# GMSL_DESERIALIZER.net
KiCad netlist of a schematic drawn in Altium Designer
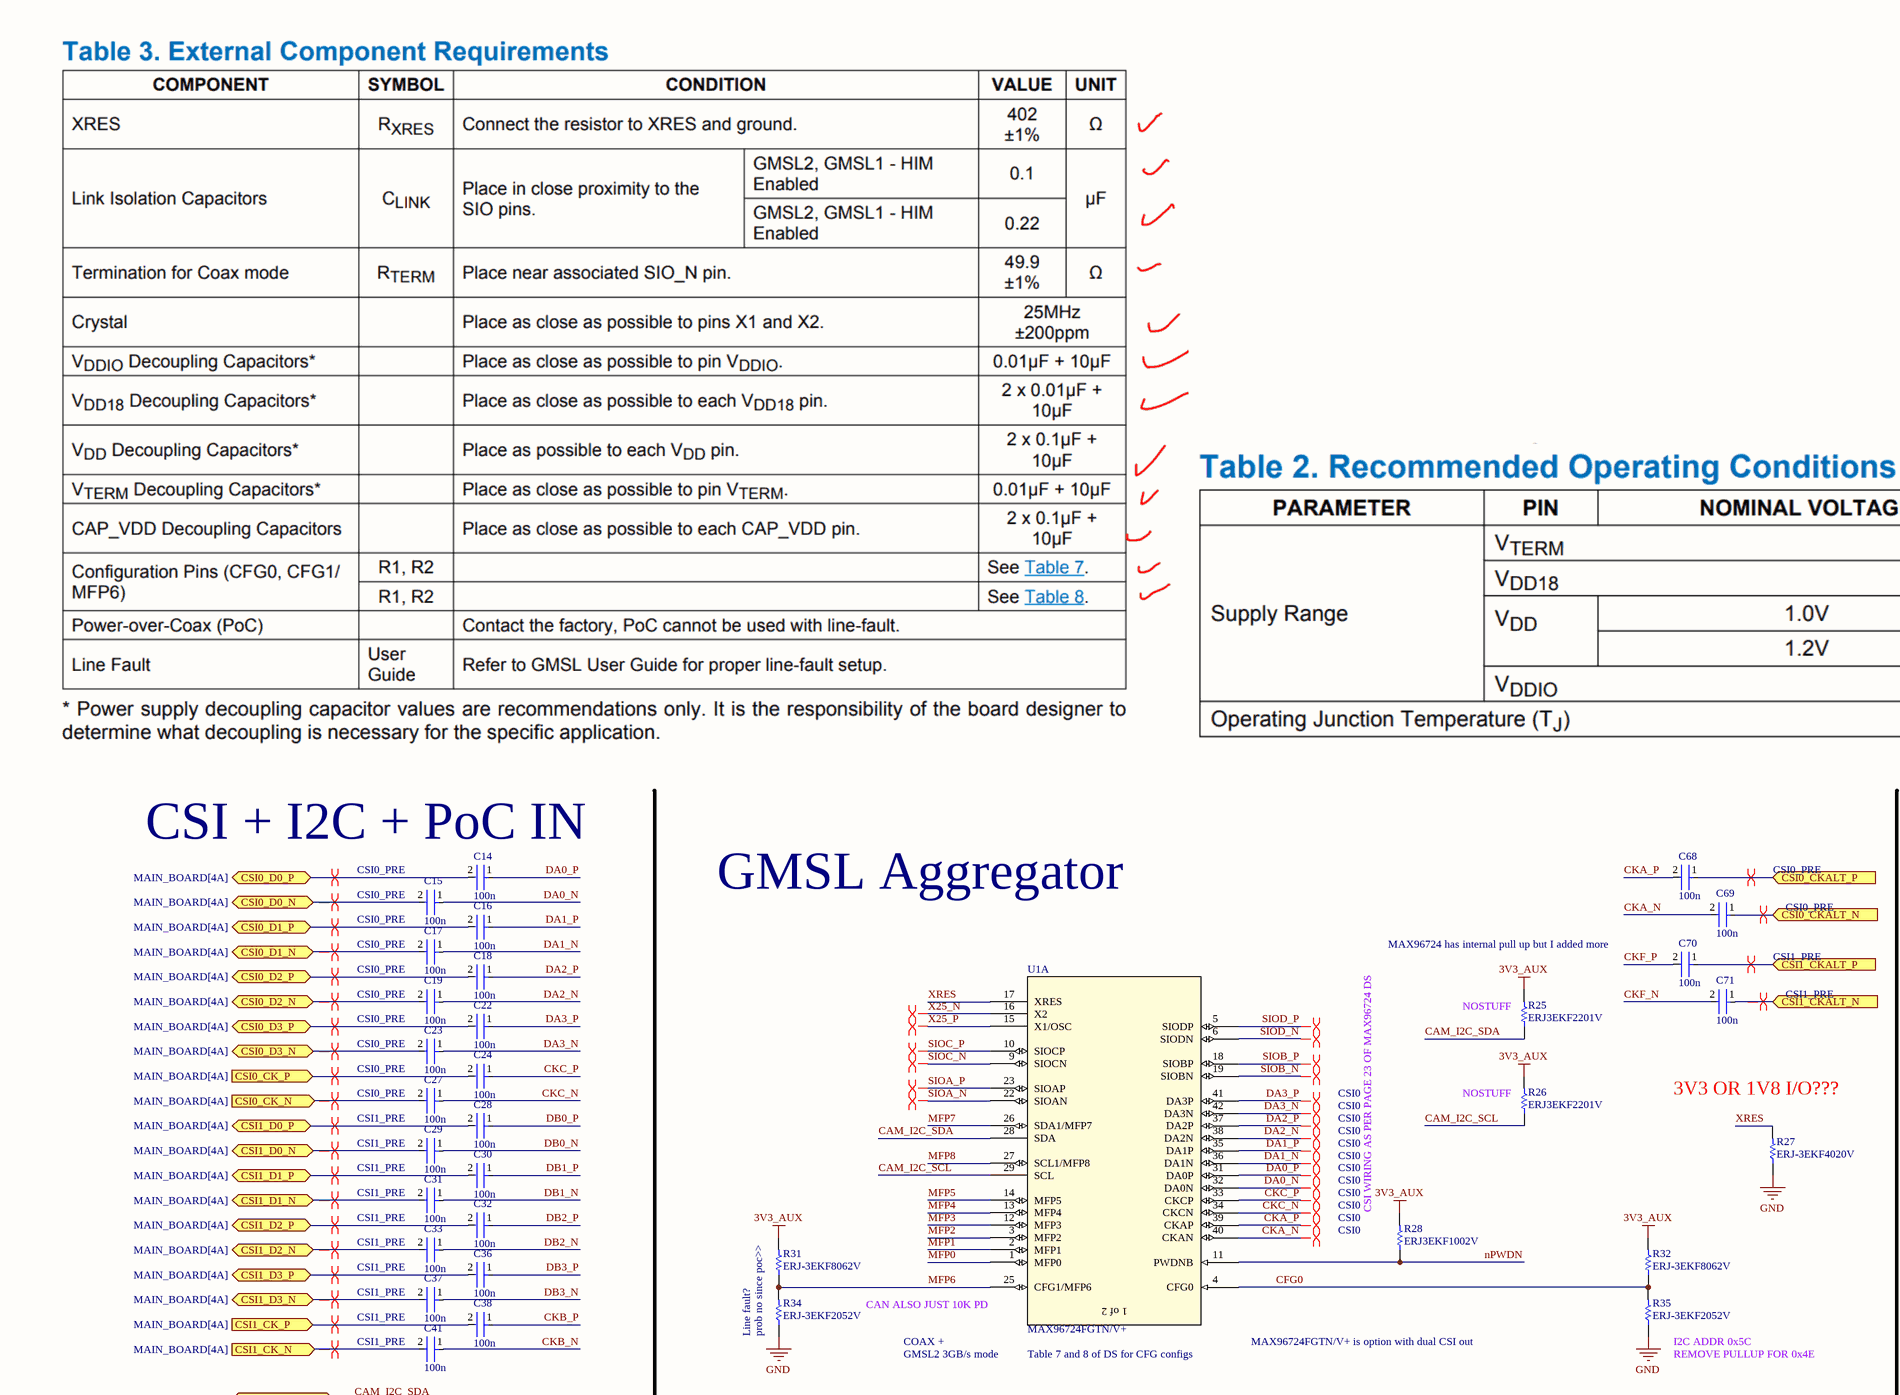
[diagram p0: GMSL_DESERIALIZER.SchDoc, top left]
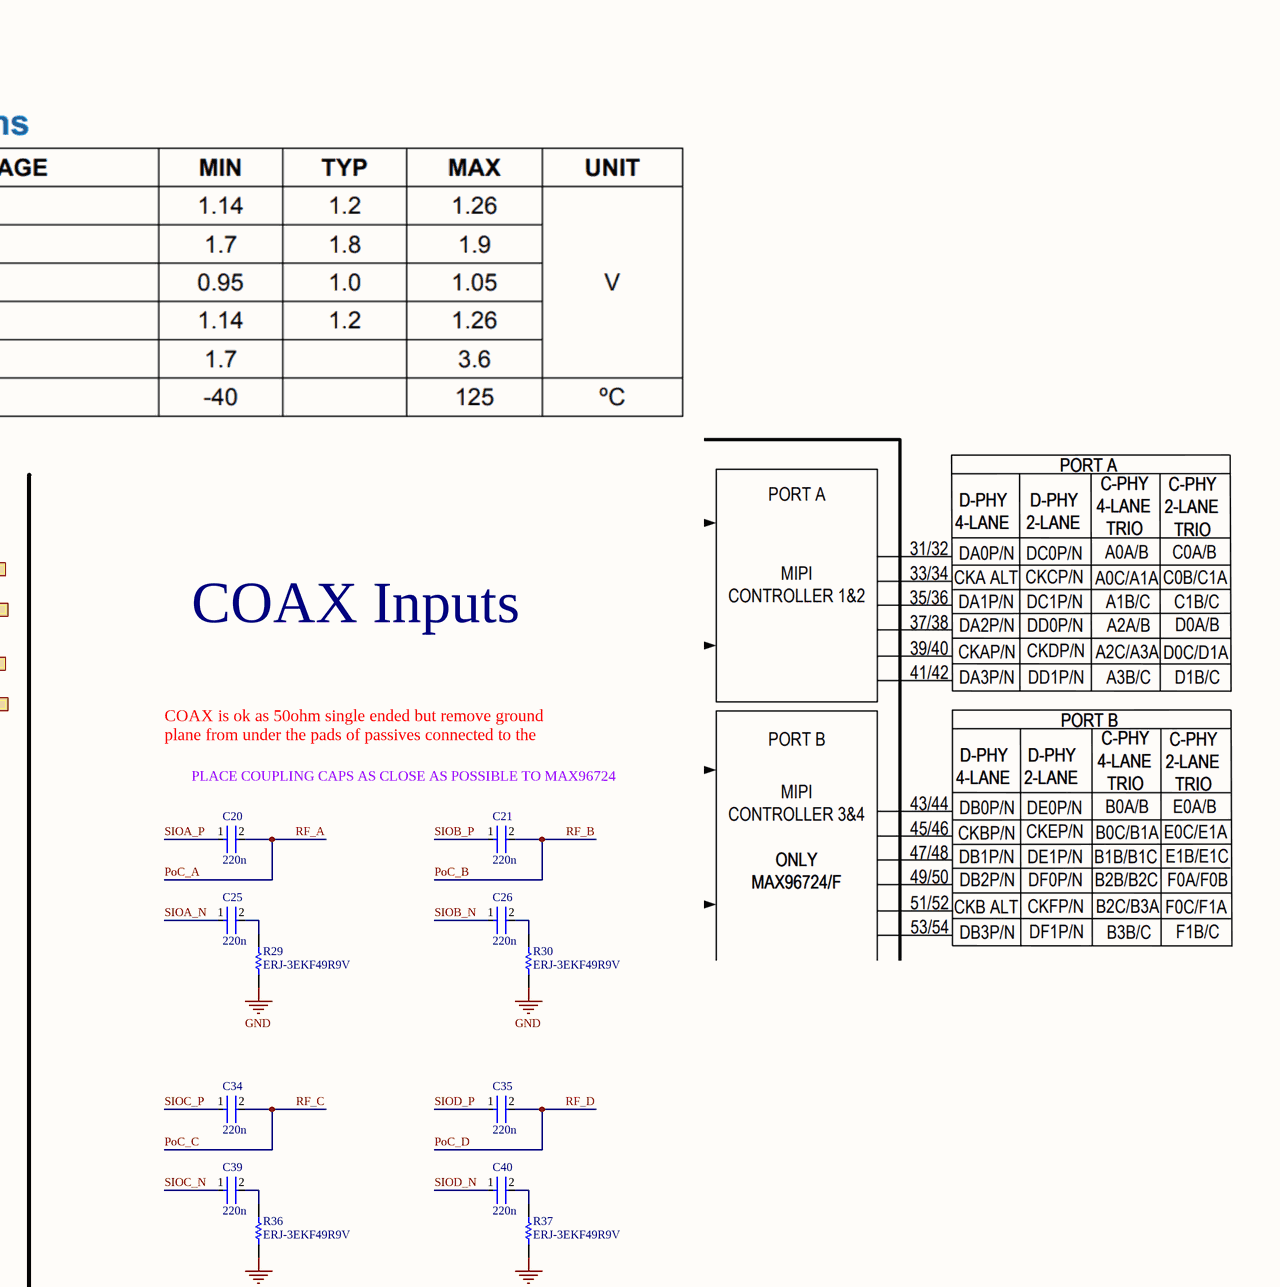
[diagram p1: GMSL_DESERIALIZER.SchDoc, top right]
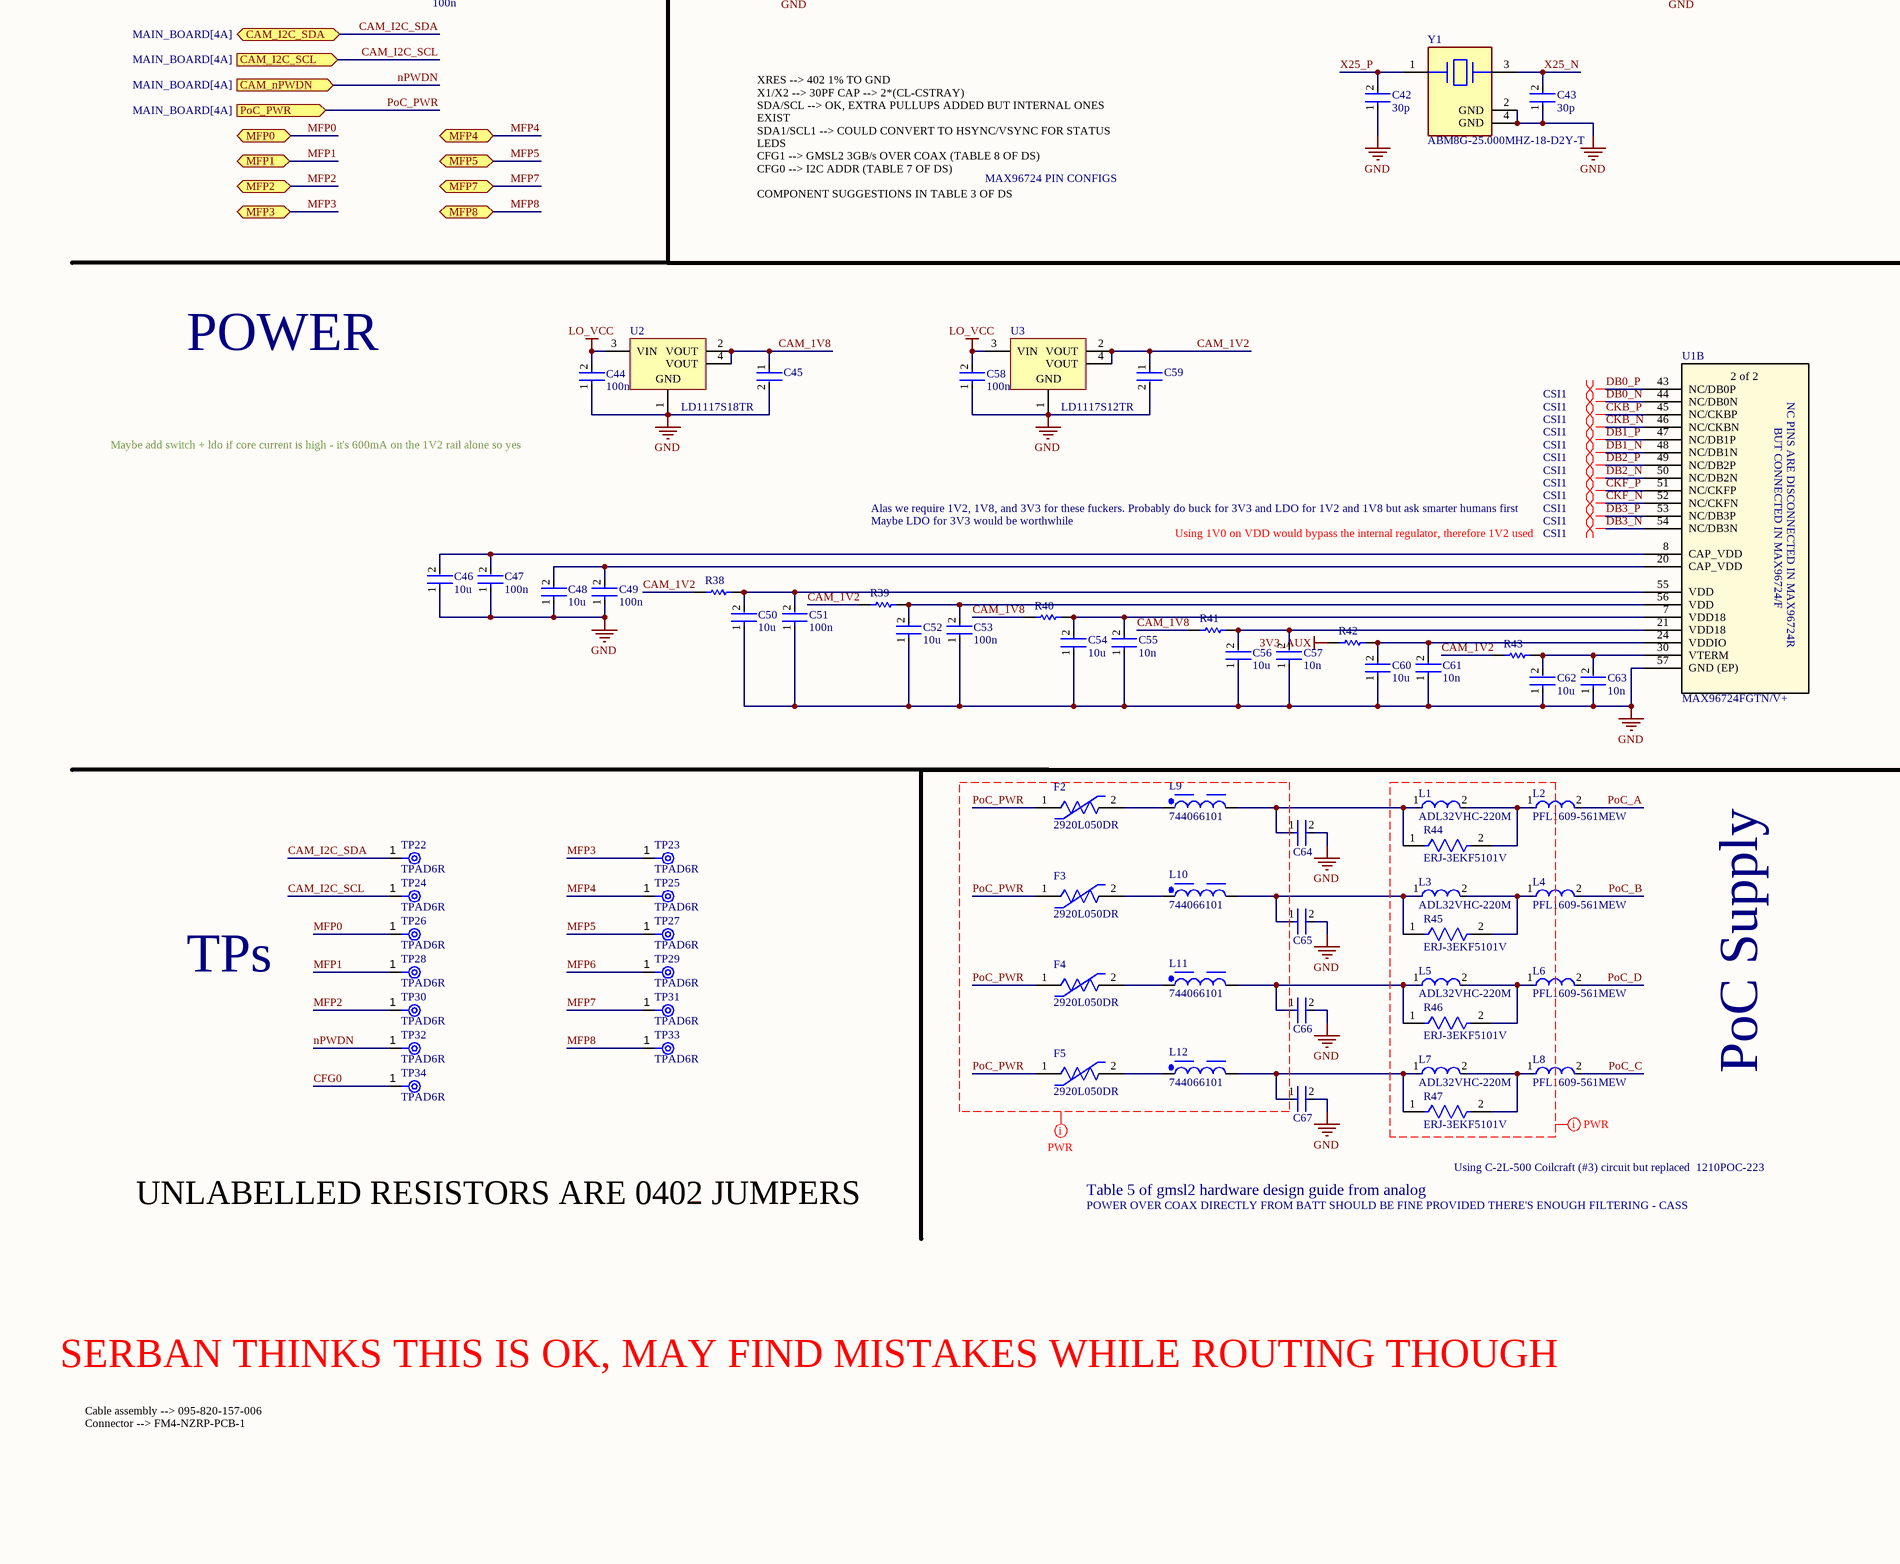
[diagram p2: GMSL_DESERIALIZER.SchDoc, bottom left]
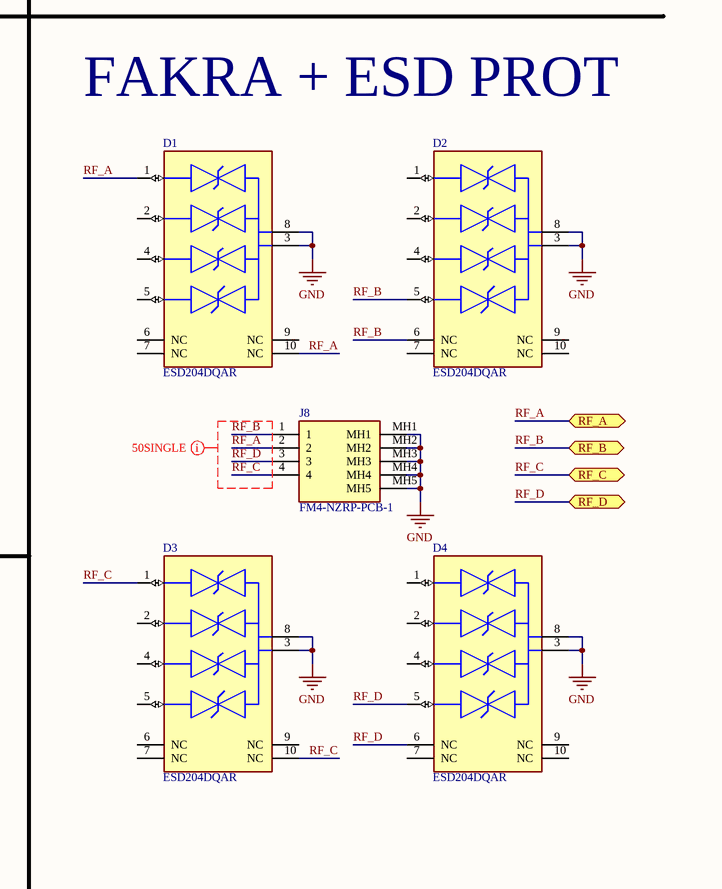
[diagram p3: GMSL_DESERIALIZER.SchDoc, bottom right]

(export (version "E")
  (design (tool "Eeschema 10.0.6"))
  (components
    (comp (ref "C14")
      (value "100n")
      (footprint "FP-0402-L_1_0_0_05-W_0_5-IPC_A")
      (description "LARGE PADS, 0402 CAP, CHANGE COMMENT TO MATCH REAL P/N")
      (libsource (lib "Space Concordia") (part "b4654b650e69147ec39a6b967a45e02"))
    )
    (comp (ref "C15")
      (value "100n")
      (footprint "FP-0402-L_1_0_0_05-W_0_5-IPC_A")
      (description "LARGE PADS, 0402 CAP, CHANGE COMMENT TO MATCH REAL P/N")
      (libsource (lib "Space Concordia") (part "b4654b650e69147ec39a6b967a45e02"))
    )
    (comp (ref "C16")
      (value "100n")
      (footprint "FP-0402-L_1_0_0_05-W_0_5-IPC_A")
      (description "LARGE PADS, 0402 CAP, CHANGE COMMENT TO MATCH REAL P/N")
      (libsource (lib "Space Concordia") (part "b4654b650e69147ec39a6b967a45e02"))
    )
    (comp (ref "C17")
      (value "100n")
      (footprint "FP-0402-L_1_0_0_05-W_0_5-IPC_A")
      (description "LARGE PADS, 0402 CAP, CHANGE COMMENT TO MATCH REAL P/N")
      (libsource (lib "Space Concordia") (part "b4654b650e69147ec39a6b967a45e02"))
    )
    (comp (ref "C18")
      (value "100n")
      (footprint "FP-0402-L_1_0_0_05-W_0_5-IPC_A")
      (description "LARGE PADS, 0402 CAP, CHANGE COMMENT TO MATCH REAL P/N")
      (libsource (lib "Space Concordia") (part "b4654b650e69147ec39a6b967a45e02"))
    )
    (comp (ref "C19")
      (value "100n")
      (footprint "FP-0402-L_1_0_0_05-W_0_5-IPC_A")
      (description "LARGE PADS, 0402 CAP, CHANGE COMMENT TO MATCH REAL P/N")
      (libsource (lib "Space Concordia") (part "b4654b650e69147ec39a6b967a45e02"))
    )
    (comp (ref "C20")
      (value "220n")
      (footprint "FP-0402-L_1_0_0_05-W_0_5-IPC_A")
      (description "LARGE PADS, 0402 CAP, CHANGE COMMENT TO MATCH REAL P/N")
      (libsource (lib "Space Concordia") (part "b4654b650e69147ec39a6b967a45e02"))
    )
    (comp (ref "C21")
      (value "220n")
      (footprint "FP-0402-L_1_0_0_05-W_0_5-IPC_A")
      (description "LARGE PADS, 0402 CAP, CHANGE COMMENT TO MATCH REAL P/N")
      (libsource (lib "Space Concordia") (part "b4654b650e69147ec39a6b967a45e02"))
    )
    (comp (ref "C22")
      (value "100n")
      (footprint "FP-0402-L_1_0_0_05-W_0_5-IPC_A")
      (description "LARGE PADS, 0402 CAP, CHANGE COMMENT TO MATCH REAL P/N")
      (libsource (lib "Space Concordia") (part "b4654b650e69147ec39a6b967a45e02"))
    )
    (comp (ref "C23")
      (value "100n")
      (footprint "FP-0402-L_1_0_0_05-W_0_5-IPC_A")
      (description "LARGE PADS, 0402 CAP, CHANGE COMMENT TO MATCH REAL P/N")
      (libsource (lib "Space Concordia") (part "b4654b650e69147ec39a6b967a45e02"))
    )
    (comp (ref "C24")
      (value "100n")
      (footprint "FP-0402-L_1_0_0_05-W_0_5-IPC_A")
      (description "LARGE PADS, 0402 CAP, CHANGE COMMENT TO MATCH REAL P/N")
      (libsource (lib "Space Concordia") (part "b4654b650e69147ec39a6b967a45e02"))
    )
    (comp (ref "C25")
      (value "220n")
      (footprint "FP-0402-L_1_0_0_05-W_0_5-IPC_A")
      (description "LARGE PADS, 0402 CAP, CHANGE COMMENT TO MATCH REAL P/N")
      (libsource (lib "Space Concordia") (part "b4654b650e69147ec39a6b967a45e02"))
    )
    (comp (ref "C26")
      (value "220n")
      (footprint "FP-0402-L_1_0_0_05-W_0_5-IPC_A")
      (description "LARGE PADS, 0402 CAP, CHANGE COMMENT TO MATCH REAL P/N")
      (libsource (lib "Space Concordia") (part "b4654b650e69147ec39a6b967a45e02"))
    )
    (comp (ref "C27")
      (value "100n")
      (footprint "FP-0402-L_1_0_0_05-W_0_5-IPC_A")
      (description "LARGE PADS, 0402 CAP, CHANGE COMMENT TO MATCH REAL P/N")
      (libsource (lib "Space Concordia") (part "b4654b650e69147ec39a6b967a45e02"))
    )
    (comp (ref "C28")
      (value "100n")
      (footprint "FP-0402-L_1_0_0_05-W_0_5-IPC_A")
      (description "LARGE PADS, 0402 CAP, CHANGE COMMENT TO MATCH REAL P/N")
      (libsource (lib "Space Concordia") (part "b4654b650e69147ec39a6b967a45e02"))
    )
    (comp (ref "C29")
      (value "100n")
      (footprint "FP-0402-L_1_0_0_05-W_0_5-IPC_A")
      (description "LARGE PADS, 0402 CAP, CHANGE COMMENT TO MATCH REAL P/N")
      (libsource (lib "Space Concordia") (part "b4654b650e69147ec39a6b967a45e02"))
    )
    (comp (ref "C30")
      (value "100n")
      (footprint "FP-0402-L_1_0_0_05-W_0_5-IPC_A")
      (description "LARGE PADS, 0402 CAP, CHANGE COMMENT TO MATCH REAL P/N")
      (libsource (lib "Space Concordia") (part "b4654b650e69147ec39a6b967a45e02"))
    )
    (comp (ref "C31")
      (value "100n")
      (footprint "FP-0402-L_1_0_0_05-W_0_5-IPC_A")
      (description "LARGE PADS, 0402 CAP, CHANGE COMMENT TO MATCH REAL P/N")
      (libsource (lib "Space Concordia") (part "b4654b650e69147ec39a6b967a45e02"))
    )
    (comp (ref "C32")
      (value "100n")
      (footprint "FP-0402-L_1_0_0_05-W_0_5-IPC_A")
      (description "LARGE PADS, 0402 CAP, CHANGE COMMENT TO MATCH REAL P/N")
      (libsource (lib "Space Concordia") (part "b4654b650e69147ec39a6b967a45e02"))
    )
    (comp (ref "C33")
      (value "100n")
      (footprint "FP-0402-L_1_0_0_05-W_0_5-IPC_A")
      (description "LARGE PADS, 0402 CAP, CHANGE COMMENT TO MATCH REAL P/N")
      (libsource (lib "Space Concordia") (part "b4654b650e69147ec39a6b967a45e02"))
    )
    (comp (ref "C34")
      (value "220n")
      (footprint "FP-0402-L_1_0_0_05-W_0_5-IPC_A")
      (description "LARGE PADS, 0402 CAP, CHANGE COMMENT TO MATCH REAL P/N")
      (libsource (lib "Space Concordia") (part "b4654b650e69147ec39a6b967a45e02"))
    )
    (comp (ref "C35")
      (value "220n")
      (footprint "FP-0402-L_1_0_0_05-W_0_5-IPC_A")
      (description "LARGE PADS, 0402 CAP, CHANGE COMMENT TO MATCH REAL P/N")
      (libsource (lib "Space Concordia") (part "b4654b650e69147ec39a6b967a45e02"))
    )
    (comp (ref "C36")
      (value "100n")
      (footprint "FP-0402-L_1_0_0_05-W_0_5-IPC_A")
      (description "LARGE PADS, 0402 CAP, CHANGE COMMENT TO MATCH REAL P/N")
      (libsource (lib "Space Concordia") (part "b4654b650e69147ec39a6b967a45e02"))
    )
    (comp (ref "C37")
      (value "100n")
      (footprint "FP-0402-L_1_0_0_05-W_0_5-IPC_A")
      (description "LARGE PADS, 0402 CAP, CHANGE COMMENT TO MATCH REAL P/N")
      (libsource (lib "Space Concordia") (part "b4654b650e69147ec39a6b967a45e02"))
    )
    (comp (ref "C38")
      (value "100n")
      (footprint "FP-0402-L_1_0_0_05-W_0_5-IPC_A")
      (description "LARGE PADS, 0402 CAP, CHANGE COMMENT TO MATCH REAL P/N")
      (libsource (lib "Space Concordia") (part "b4654b650e69147ec39a6b967a45e02"))
    )
    (comp (ref "C39")
      (value "220n")
      (footprint "FP-0402-L_1_0_0_05-W_0_5-IPC_A")
      (description "LARGE PADS, 0402 CAP, CHANGE COMMENT TO MATCH REAL P/N")
      (libsource (lib "Space Concordia") (part "b4654b650e69147ec39a6b967a45e02"))
    )
    (comp (ref "C40")
      (value "220n")
      (footprint "FP-0402-L_1_0_0_05-W_0_5-IPC_A")
      (description "LARGE PADS, 0402 CAP, CHANGE COMMENT TO MATCH REAL P/N")
      (libsource (lib "Space Concordia") (part "b4654b650e69147ec39a6b967a45e02"))
    )
    (comp (ref "C41")
      (value "100n")
      (footprint "FP-0402-L_1_0_0_05-W_0_5-IPC_A")
      (description "LARGE PADS, 0402 CAP, CHANGE COMMENT TO MATCH REAL P/N")
      (libsource (lib "Space Concordia") (part "b4654b650e69147ec39a6b967a45e02"))
    )
    (comp (ref "C42")
      (value "30p")
      (footprint "FP-0402-L_1_0_0_05-W_0_5-IPC_A")
      (description "LARGE PADS, 0402 CAP, CHANGE COMMENT TO MATCH REAL P/N")
      (libsource (lib "Space Concordia") (part "b4654b650e69147ec39a6b967a45e02"))
    )
    (comp (ref "C43")
      (value "30p")
      (footprint "FP-0402-L_1_0_0_05-W_0_5-IPC_A")
      (description "LARGE PADS, 0402 CAP, CHANGE COMMENT TO MATCH REAL P/N")
      (libsource (lib "Space Concordia") (part "b4654b650e69147ec39a6b967a45e02"))
    )
    (comp (ref "C44")
      (value "100n")
      (footprint "FP-0402-L_1_0_0_05-W_0_5-IPC_A")
      (description "LARGE PADS, 0402 CAP, CHANGE COMMENT TO MATCH REAL P/N")
      (libsource (lib "Space Concordia") (part "b4654b650e69147ec39a6b967a45e02"))
    )
    (comp (ref "C45")
      (value "GRM188R60J106ME47D")
      (footprint "FP-GRM188-0_1-e0_2_0_55-IPC_A")
      (description "Chip Multilayer Ceramic Capacitors for General Purpose, 0603, 10uF, X5R, 15%, 20%, 6.3V")
      (fields (field (name "VOLTAGE") "6.3V") (field (name "TOLERANCE") "20%"))
      (libsource (lib "Altium Content Vault") (part "02cd4be3c70576c341d710602a673aa"))
    )
    (comp (ref "C46")
      (value "10u")
      (footprint "FP-0402-L_1_0_0_05-W_0_5-IPC_A")
      (description "LARGE PADS, 0402 CAP, CHANGE COMMENT TO MATCH REAL P/N")
      (libsource (lib "Space Concordia") (part "b4654b650e69147ec39a6b967a45e02"))
    )
    (comp (ref "C47")
      (value "100n")
      (footprint "FP-0402-L_1_0_0_05-W_0_5-IPC_A")
      (description "LARGE PADS, 0402 CAP, CHANGE COMMENT TO MATCH REAL P/N")
      (libsource (lib "Space Concordia") (part "b4654b650e69147ec39a6b967a45e02"))
    )
    (comp (ref "C48")
      (value "10u")
      (footprint "FP-0402-L_1_0_0_05-W_0_5-IPC_A")
      (description "LARGE PADS, 0402 CAP, CHANGE COMMENT TO MATCH REAL P/N")
      (libsource (lib "Space Concordia") (part "b4654b650e69147ec39a6b967a45e02"))
    )
    (comp (ref "C49")
      (value "100n")
      (footprint "FP-0402-L_1_0_0_05-W_0_5-IPC_A")
      (description "LARGE PADS, 0402 CAP, CHANGE COMMENT TO MATCH REAL P/N")
      (libsource (lib "Space Concordia") (part "b4654b650e69147ec39a6b967a45e02"))
    )
    (comp (ref "C50")
      (value "10u")
      (footprint "FP-0402-L_1_0_0_05-W_0_5-IPC_A")
      (description "LARGE PADS, 0402 CAP, CHANGE COMMENT TO MATCH REAL P/N")
      (libsource (lib "Space Concordia") (part "b4654b650e69147ec39a6b967a45e02"))
    )
    (comp (ref "C51")
      (value "100n")
      (footprint "FP-0402-L_1_0_0_05-W_0_5-IPC_A")
      (description "LARGE PADS, 0402 CAP, CHANGE COMMENT TO MATCH REAL P/N")
      (libsource (lib "Space Concordia") (part "b4654b650e69147ec39a6b967a45e02"))
    )
    (comp (ref "C52")
      (value "10u")
      (footprint "FP-0402-L_1_0_0_05-W_0_5-IPC_A")
      (description "LARGE PADS, 0402 CAP, CHANGE COMMENT TO MATCH REAL P/N")
      (libsource (lib "Space Concordia") (part "b4654b650e69147ec39a6b967a45e02"))
    )
    (comp (ref "C53")
      (value "100n")
      (footprint "FP-0402-L_1_0_0_05-W_0_5-IPC_A")
      (description "LARGE PADS, 0402 CAP, CHANGE COMMENT TO MATCH REAL P/N")
      (libsource (lib "Space Concordia") (part "b4654b650e69147ec39a6b967a45e02"))
    )
    (comp (ref "C54")
      (value "10u")
      (footprint "FP-0402-L_1_0_0_05-W_0_5-IPC_A")
      (description "LARGE PADS, 0402 CAP, CHANGE COMMENT TO MATCH REAL P/N")
      (libsource (lib "Space Concordia") (part "b4654b650e69147ec39a6b967a45e02"))
    )
    (comp (ref "C55")
      (value "10n")
      (footprint "FP-0402-L_1_0_0_05-W_0_5-IPC_A")
      (description "LARGE PADS, 0402 CAP, CHANGE COMMENT TO MATCH REAL P/N")
      (libsource (lib "Space Concordia") (part "b4654b650e69147ec39a6b967a45e02"))
    )
    (comp (ref "C56")
      (value "10u")
      (footprint "FP-0402-L_1_0_0_05-W_0_5-IPC_A")
      (description "LARGE PADS, 0402 CAP, CHANGE COMMENT TO MATCH REAL P/N")
      (libsource (lib "Space Concordia") (part "b4654b650e69147ec39a6b967a45e02"))
    )
    (comp (ref "C57")
      (value "10n")
      (footprint "FP-0402-L_1_0_0_05-W_0_5-IPC_A")
      (description "LARGE PADS, 0402 CAP, CHANGE COMMENT TO MATCH REAL P/N")
      (libsource (lib "Space Concordia") (part "b4654b650e69147ec39a6b967a45e02"))
    )
    (comp (ref "C58")
      (value "100n")
      (footprint "FP-0402-L_1_0_0_05-W_0_5-IPC_A")
      (description "LARGE PADS, 0402 CAP, CHANGE COMMENT TO MATCH REAL P/N")
      (libsource (lib "Space Concordia") (part "b4654b650e69147ec39a6b967a45e02"))
    )
    (comp (ref "C59")
      (value "GRM188R60J106ME47D")
      (footprint "FP-GRM188-0_1-e0_2_0_55-IPC_A")
      (description "Chip Multilayer Ceramic Capacitors for General Purpose, 0603, 10uF, X5R, 15%, 20%, 6.3V")
      (fields (field (name "VOLTAGE") "6.3V") (field (name "TOLERANCE") "20%"))
      (libsource (lib "Altium Content Vault") (part "02cd4be3c70576c341d710602a673aa"))
    )
    (comp (ref "C60")
      (value "10u")
      (footprint "FP-0402-L_1_0_0_05-W_0_5-IPC_A")
      (description "LARGE PADS, 0402 CAP, CHANGE COMMENT TO MATCH REAL P/N")
      (libsource (lib "Space Concordia") (part "b4654b650e69147ec39a6b967a45e02"))
    )
    (comp (ref "C61")
      (value "10n")
      (footprint "FP-0402-L_1_0_0_05-W_0_5-IPC_A")
      (description "LARGE PADS, 0402 CAP, CHANGE COMMENT TO MATCH REAL P/N")
      (libsource (lib "Space Concordia") (part "b4654b650e69147ec39a6b967a45e02"))
    )
    (comp (ref "C62")
      (value "10u")
      (footprint "FP-0402-L_1_0_0_05-W_0_5-IPC_A")
      (description "LARGE PADS, 0402 CAP, CHANGE COMMENT TO MATCH REAL P/N")
      (libsource (lib "Space Concordia") (part "b4654b650e69147ec39a6b967a45e02"))
    )
    (comp (ref "C63")
      (value "10n")
      (footprint "FP-0402-L_1_0_0_05-W_0_5-IPC_A")
      (description "LARGE PADS, 0402 CAP, CHANGE COMMENT TO MATCH REAL P/N")
      (libsource (lib "Space Concordia") (part "b4654b650e69147ec39a6b967a45e02"))
    )
    (comp (ref "C64")
      (value "GRM21BR61E226ME44L")
      (footprint "FP-GRM21B-0_2-e0_2_0_7-IPC_B")
      (description "Chip Multilayer Ceramic Capacitors for General Purpose, 0805, 22uF, X5R, 15%, 20%, 25V")
      (fields (field (name "TOLERANCE") "20%") (field (name "VOLTAGE") "25V"))
      (libsource (lib "Altium Content Vault") (part "b4654b650e69147ec39a6b967a45e02"))
    )
    (comp (ref "C65")
      (value "GRM21BR61E226ME44L")
      (footprint "FP-GRM21B-0_2-e0_2_0_7-IPC_B")
      (description "Chip Multilayer Ceramic Capacitors for General Purpose, 0805, 22uF, X5R, 15%, 20%, 25V")
      (fields (field (name "TOLERANCE") "20%") (field (name "VOLTAGE") "25V"))
      (libsource (lib "Altium Content Vault") (part "b4654b650e69147ec39a6b967a45e02"))
    )
    (comp (ref "C66")
      (value "GRM21BR61E226ME44L")
      (footprint "FP-GRM21B-0_2-e0_2_0_7-IPC_B")
      (description "Chip Multilayer Ceramic Capacitors for General Purpose, 0805, 22uF, X5R, 15%, 20%, 25V")
      (fields (field (name "TOLERANCE") "20%") (field (name "VOLTAGE") "25V"))
      (libsource (lib "Altium Content Vault") (part "b4654b650e69147ec39a6b967a45e02"))
    )
    (comp (ref "C67")
      (value "GRM21BR61E226ME44L")
      (footprint "FP-GRM21B-0_2-e0_2_0_7-IPC_B")
      (description "Chip Multilayer Ceramic Capacitors for General Purpose, 0805, 22uF, X5R, 15%, 20%, 25V")
      (fields (field (name "TOLERANCE") "20%") (field (name "VOLTAGE") "25V"))
      (libsource (lib "Altium Content Vault") (part "b4654b650e69147ec39a6b967a45e02"))
    )
    (comp (ref "C68")
      (value "100n")
      (footprint "FP-0402-L_1_0_0_05-W_0_5-IPC_A")
      (description "LARGE PADS, 0402 CAP, CHANGE COMMENT TO MATCH REAL P/N")
      (libsource (lib "Space Concordia") (part "b4654b650e69147ec39a6b967a45e02"))
    )
    (comp (ref "C69")
      (value "100n")
      (footprint "FP-0402-L_1_0_0_05-W_0_5-IPC_A")
      (description "LARGE PADS, 0402 CAP, CHANGE COMMENT TO MATCH REAL P/N")
      (libsource (lib "Space Concordia") (part "b4654b650e69147ec39a6b967a45e02"))
    )
    (comp (ref "C70")
      (value "100n")
      (footprint "FP-0402-L_1_0_0_05-W_0_5-IPC_A")
      (description "LARGE PADS, 0402 CAP, CHANGE COMMENT TO MATCH REAL P/N")
      (libsource (lib "Space Concordia") (part "b4654b650e69147ec39a6b967a45e02"))
    )
    (comp (ref "C71")
      (value "100n")
      (footprint "FP-0402-L_1_0_0_05-W_0_5-IPC_A")
      (description "LARGE PADS, 0402 CAP, CHANGE COMMENT TO MATCH REAL P/N")
      (libsource (lib "Space Concordia") (part "b4654b650e69147ec39a6b967a45e02"))
    )
    (comp (ref "D1")
      (value "ESD204DQAR")
      (footprint "FP-DQA0010A-MFG")
      (description "4-CHANNEL LOW-CAPACITANCE SURGE")
      (fields
        (field (name "MANUFACTURER") "Texas Instruments")
        (field (name "OCTOPART") "https://octopart.com/esd204dqar-texas+instruments-89917476")
      )
      (libsource (lib "Altium Content Vault") (part "1465e58c1818c7767b55926832f0bf5"))
    )
    (comp (ref "D2")
      (value "ESD204DQAR")
      (footprint "FP-DQA0010A-MFG")
      (description "4-CHANNEL LOW-CAPACITANCE SURGE")
      (fields
        (field (name "MANUFACTURER") "Texas Instruments")
        (field (name "OCTOPART") "https://octopart.com/esd204dqar-texas+instruments-89917476")
      )
      (libsource (lib "Altium Content Vault") (part "1465e58c1818c7767b55926832f0bf5"))
    )
    (comp (ref "D3")
      (value "ESD204DQAR")
      (footprint "FP-DQA0010A-MFG")
      (description "4-CHANNEL LOW-CAPACITANCE SURGE")
      (fields
        (field (name "MANUFACTURER") "Texas Instruments")
        (field (name "OCTOPART") "https://octopart.com/esd204dqar-texas+instruments-89917476")
      )
      (libsource (lib "Altium Content Vault") (part "1465e58c1818c7767b55926832f0bf5"))
    )
    (comp (ref "D4")
      (value "ESD204DQAR")
      (footprint "FP-DQA0010A-MFG")
      (description "4-CHANNEL LOW-CAPACITANCE SURGE")
      (fields
        (field (name "MANUFACTURER") "Texas Instruments")
        (field (name "OCTOPART") "https://octopart.com/esd204dqar-texas+instruments-89917476")
      )
      (libsource (lib "Altium Content Vault") (part "1465e58c1818c7767b55926832f0bf5"))
    )
    (comp (ref "F2")
      (value "2920L050DR")
      (footprint "FP-2920L050DR-MFG")
      (description "PTC RESET FUSE 60V 500MA 2920")
      (libsource (lib "Altium Content Vault") (part "1c6d77a0208143737455a0c7eb396be"))
    )
    (comp (ref "F3")
      (value "2920L050DR")
      (footprint "FP-2920L050DR-MFG")
      (description "PTC RESET FUSE 60V 500MA 2920")
      (libsource (lib "Altium Content Vault") (part "1c6d77a0208143737455a0c7eb396be"))
    )
    (comp (ref "F4")
      (value "2920L050DR")
      (footprint "FP-2920L050DR-MFG")
      (description "PTC RESET FUSE 60V 500MA 2920")
      (libsource (lib "Altium Content Vault") (part "1c6d77a0208143737455a0c7eb396be"))
    )
    (comp (ref "F5")
      (value "2920L050DR")
      (footprint "FP-2920L050DR-MFG")
      (description "PTC RESET FUSE 60V 500MA 2920")
      (libsource (lib "Altium Content Vault") (part "1c6d77a0208143737455a0c7eb396be"))
    )
    (comp (ref "J8")
      (value "FM4-NZRP-PCB-1")
      (footprint "FM4-NZRP-PCB-1-Footprint-1")
      (description "Connector RF Mini-FAKRA Plug 9GHz 50Ohm Solder Right Angle Through Hole")
      (libsource (lib "Space Concordia") (part "CMP-002-00085-1"))
    )
    (comp (ref "L1")
      (value "ADL32VHC-220M")
      (footprint "FP-1210POC-MFG")
      (description "NOT COILCRAFT - ACTUAL P# --> ADL32VHC-220M\r\n - Power Injection Chokes for PoC")
      (fields
        (field (name "MANUFACTURER") "coilcraft")
        (field (name "OCTOPART") "https://octopart.com/1210poc-223mrc-coilcraft-103207315")
      )
      (libsource (lib "Altium Content Vault") (part "725321dda6339637d4d059423bc1c3c"))
    )
    (comp (ref "L2")
      (value "PFL1609-561MEW")
      (footprint "FP-PFL1609-MFG")
      (description "Fixed Inductors PFL1609 Low Profile 0.56 uH 20 % 1.4 A")
      (fields (field (name "MANUFACTURER") "coilcraft") (field (name "TOLERANCE") "20%"))
      (libsource (lib "Altium Content Vault") (part "725321dda6339637d4d059423bc1c3c"))
    )
    (comp (ref "L3")
      (value "ADL32VHC-220M")
      (footprint "FP-1210POC-MFG")
      (description "NOT COILCRAFT - ACTUAL P# --> ADL32VHC-220M\r\n - Power Injection Chokes for PoC")
      (fields
        (field (name "MANUFACTURER") "coilcraft")
        (field (name "OCTOPART") "https://octopart.com/1210poc-223mrc-coilcraft-103207315")
      )
      (libsource (lib "Altium Content Vault") (part "725321dda6339637d4d059423bc1c3c"))
    )
    (comp (ref "L4")
      (value "PFL1609-561MEW")
      (footprint "FP-PFL1609-MFG")
      (description "Fixed Inductors PFL1609 Low Profile 0.56 uH 20 % 1.4 A")
      (fields (field (name "MANUFACTURER") "coilcraft") (field (name "TOLERANCE") "20%"))
      (libsource (lib "Altium Content Vault") (part "725321dda6339637d4d059423bc1c3c"))
    )
    (comp (ref "L5")
      (value "ADL32VHC-220M")
      (footprint "FP-1210POC-MFG")
      (description "NOT COILCRAFT - ACTUAL P# --> ADL32VHC-220M\r\n - Power Injection Chokes for PoC")
      (fields
        (field (name "MANUFACTURER") "coilcraft")
        (field (name "OCTOPART") "https://octopart.com/1210poc-223mrc-coilcraft-103207315")
      )
      (libsource (lib "Altium Content Vault") (part "725321dda6339637d4d059423bc1c3c"))
    )
    (comp (ref "L6")
      (value "PFL1609-561MEW")
      (footprint "FP-PFL1609-MFG")
      (description "Fixed Inductors PFL1609 Low Profile 0.56 uH 20 % 1.4 A")
      (fields (field (name "MANUFACTURER") "coilcraft") (field (name "TOLERANCE") "20%"))
      (libsource (lib "Altium Content Vault") (part "725321dda6339637d4d059423bc1c3c"))
    )
    (comp (ref "L7")
      (value "ADL32VHC-220M")
      (footprint "FP-1210POC-MFG")
      (description "NOT COILCRAFT - ACTUAL P# --> ADL32VHC-220M\r\n - Power Injection Chokes for PoC")
      (fields
        (field (name "MANUFACTURER") "coilcraft")
        (field (name "OCTOPART") "https://octopart.com/1210poc-223mrc-coilcraft-103207315")
      )
      (libsource (lib "Altium Content Vault") (part "725321dda6339637d4d059423bc1c3c"))
    )
    (comp (ref "L8")
      (value "PFL1609-561MEW")
      (footprint "FP-PFL1609-MFG")
      (description "Fixed Inductors PFL1609 Low Profile 0.56 uH 20 % 1.4 A")
      (fields (field (name "MANUFACTURER") "coilcraft") (field (name "TOLERANCE") "20%"))
      (libsource (lib "Altium Content Vault") (part "725321dda6339637d4d059423bc1c3c"))
    )
    (comp (ref "L9")
      (value "744066101")
      (footprint "WE-TPC_1038")
      (fields (field (name "TOLERANCE") "30%"))
      (libsource (lib "Altium Content Vault") (part "Inductor - 2"))
    )
    (comp (ref "L10")
      (value "744066101")
      (footprint "WE-TPC_1038")
      (fields (field (name "TOLERANCE") "30%"))
      (libsource (lib "Altium Content Vault") (part "Inductor - 2"))
    )
    (comp (ref "L11")
      (value "744066101")
      (footprint "WE-TPC_1038")
      (fields (field (name "TOLERANCE") "30%"))
      (libsource (lib "Altium Content Vault") (part "Inductor - 2"))
    )
    (comp (ref "L12")
      (value "744066101")
      (footprint "WE-TPC_1038")
      (fields (field (name "TOLERANCE") "30%"))
      (libsource (lib "Altium Content Vault") (part "Inductor - 2"))
    )
    (comp (ref "R25")
      (value "ERJ3EKF2201V")
      (footprint "RESC1608X55X30LL15T15")
      (fields (field (name "MANUFACTURER") "Panasonic"))
      (libsource (lib "Altium Content Vault") (part "RES"))
    )
    (comp (ref "R26")
      (value "ERJ3EKF2201V")
      (footprint "RESC1608X55X30LL15T15")
      (fields (field (name "MANUFACTURER") "Panasonic"))
      (libsource (lib "Altium Content Vault") (part "RES"))
    )
    (comp (ref "R27")
      (value "ERJ-3EKF4020V")
      (footprint "RESC1608X55X30LL15T15")
      (fields (field (name "MANUFACTURER") "Panasonic"))
      (libsource (lib "Altium Content Vault") (part "RES"))
    )
    (comp (ref "R28")
      (value "ERJ3EKF1002V")
      (footprint "RESC1609X55X30LL15T15")
      (description "Chip Resistor, 10 KOhm, +/- 1%, 0.1 W, -55 to 155 degC, 0603 (1608 Metric), RoHS, Tape and Reel")
      (fields (field (name "TOLERANCE") "1%") (field (name "MANUFACTURER") "Panasonic"))
      (libsource (lib "Altium Content Vault") (part "RES-2"))
    )
    (comp (ref "R29")
      (value "ERJ-3EKF49R9V")
      (footprint "RESC1608X55X30ML15T15")
      (fields (field (name "MANUFACTURER") "Panasonic"))
      (libsource (lib "Altium Content Vault") (part "RES"))
    )
    (comp (ref "R30")
      (value "ERJ-3EKF49R9V")
      (footprint "RESC1608X55X30ML15T15")
      (fields (field (name "MANUFACTURER") "Panasonic"))
      (libsource (lib "Altium Content Vault") (part "RES"))
    )
    (comp (ref "R31")
      (value "ERJ-3EKF8062V")
      (footprint "RESC1608X55X30LL15T15")
      (fields (field (name "MANUFACTURER") "Panasonic"))
      (libsource (lib "Altium Content Vault") (part "RES"))
    )
    (comp (ref "R32")
      (value "ERJ-3EKF8062V")
      (footprint "RESC1608X55X30LL15T15")
      (fields (field (name "MANUFACTURER") "Panasonic"))
      (libsource (lib "Altium Content Vault") (part "RES"))
    )
    (comp (ref "R34")
      (value "ERJ-3EKF2052V")
      (footprint "RESC1608X55X30NL15T15")
      (fields (field (name "MANUFACTURER") "Panasonic"))
      (libsource (lib "Altium Content Vault") (part "RES"))
    )
    (comp (ref "R35")
      (value "ERJ-3EKF2052V")
      (footprint "RESC1608X55X30NL15T15")
      (fields (field (name "MANUFACTURER") "Panasonic"))
      (libsource (lib "Altium Content Vault") (part "RES"))
    )
    (comp (ref "R36")
      (value "ERJ-3EKF49R9V")
      (footprint "RESC1608X55X30ML15T15")
      (fields (field (name "MANUFACTURER") "Panasonic"))
      (libsource (lib "Altium Content Vault") (part "RES"))
    )
    (comp (ref "R37")
      (value "ERJ-3EKF49R9V")
      (footprint "RESC1608X55X30ML15T15")
      (fields (field (name "MANUFACTURER") "Panasonic"))
      (libsource (lib "Altium Content Vault") (part "RES"))
    )
    (comp (ref "R38")
      (value "RC0402JR-070RL")
      (footprint "RESC1005X40X25NL05T10")
      (fields (field (name "MANUFACTURER") "Yageo / Phycomp"))
      (libsource (lib "Altium Content Vault") (part "RES"))
    )
    (comp (ref "R39")
      (value "RC0402JR-070RL")
      (footprint "RESC1005X40X25NL05T10")
      (fields (field (name "MANUFACTURER") "Yageo / Phycomp"))
      (libsource (lib "Altium Content Vault") (part "RES"))
    )
    (comp (ref "R40")
      (value "RC0402JR-070RL")
      (footprint "RESC1005X40X25NL05T10")
      (fields (field (name "MANUFACTURER") "Yageo / Phycomp"))
      (libsource (lib "Altium Content Vault") (part "RES"))
    )
    (comp (ref "R41")
      (value "RC0402JR-070RL")
      (footprint "RESC1005X40X25NL05T10")
      (fields (field (name "MANUFACTURER") "Yageo / Phycomp"))
      (libsource (lib "Altium Content Vault") (part "RES"))
    )
    (comp (ref "R42")
      (value "RC0402JR-070RL")
      (footprint "RESC1005X40X25NL05T10")
      (fields (field (name "MANUFACTURER") "Yageo / Phycomp"))
      (libsource (lib "Altium Content Vault") (part "RES"))
    )
    (comp (ref "R43")
      (value "RC0402JR-070RL")
      (footprint "RESC1005X40X25NL05T10")
      (fields (field (name "MANUFACTURER") "Yageo / Phycomp"))
      (libsource (lib "Altium Content Vault") (part "RES"))
    )
    (comp (ref "R44")
      (value "ERJ-3EKF5101V")
      (footprint "FP-ERJ3EK-MFG")
      (description "RES SMD 5.1K OHM 1% 1/10W 0603")
      (fields (field (name "TOLERANCE") "1%"))
      (libsource (lib "Altium Content Vault") (part "1029c3af85768c4190bb7ad29bc67b5"))
    )
    (comp (ref "R45")
      (value "ERJ-3EKF5101V")
      (footprint "FP-ERJ3EK-MFG")
      (description "RES SMD 5.1K OHM 1% 1/10W 0603")
      (fields (field (name "TOLERANCE") "1%"))
      (libsource (lib "Altium Content Vault") (part "1029c3af85768c4190bb7ad29bc67b5"))
    )
    (comp (ref "R46")
      (value "ERJ-3EKF5101V")
      (footprint "FP-ERJ3EK-MFG")
      (description "RES SMD 5.1K OHM 1% 1/10W 0603")
      (fields (field (name "TOLERANCE") "1%"))
      (libsource (lib "Altium Content Vault") (part "1029c3af85768c4190bb7ad29bc67b5"))
    )
    (comp (ref "R47")
      (value "ERJ-3EKF5101V")
      (footprint "FP-ERJ3EK-MFG")
      (description "RES SMD 5.1K OHM 1% 1/10W 0603")
      (fields (field (name "TOLERANCE") "1%"))
      (libsource (lib "Altium Content Vault") (part "1029c3af85768c4190bb7ad29bc67b5"))
    )
    (comp (ref "TP22")
      (value "TPAD6R")
      (footprint "New footprint 1")
      (description "Test Point .6mm")
      (libsource (lib "Space Concordia") (part "TP"))
    )
    (comp (ref "TP23")
      (value "TPAD6R")
      (footprint "New footprint 1")
      (description "Test Point .6mm")
      (libsource (lib "Space Concordia") (part "TP"))
    )
    (comp (ref "TP24")
      (value "TPAD6R")
      (footprint "New footprint 1")
      (description "Test Point .6mm")
      (libsource (lib "Space Concordia") (part "TP"))
    )
    (comp (ref "TP25")
      (value "TPAD6R")
      (footprint "New footprint 1")
      (description "Test Point .6mm")
      (libsource (lib "Space Concordia") (part "TP"))
    )
    (comp (ref "TP26")
      (value "TPAD6R")
      (footprint "New footprint 1")
      (description "Test Point .6mm")
      (libsource (lib "Space Concordia") (part "TP"))
    )
    (comp (ref "TP27")
      (value "TPAD6R")
      (footprint "New footprint 1")
      (description "Test Point .6mm")
      (libsource (lib "Space Concordia") (part "TP"))
    )
    (comp (ref "TP28")
      (value "TPAD6R")
      (footprint "New footprint 1")
      (description "Test Point .6mm")
      (libsource (lib "Space Concordia") (part "TP"))
    )
    (comp (ref "TP29")
      (value "TPAD6R")
      (footprint "New footprint 1")
      (description "Test Point .6mm")
      (libsource (lib "Space Concordia") (part "TP"))
    )
    (comp (ref "TP30")
      (value "TPAD6R")
      (footprint "New footprint 1")
      (description "Test Point .6mm")
      (libsource (lib "Space Concordia") (part "TP"))
    )
    (comp (ref "TP31")
      (value "TPAD6R")
      (footprint "New footprint 1")
      (description "Test Point .6mm")
      (libsource (lib "Space Concordia") (part "TP"))
    )
    (comp (ref "TP32")
      (value "TPAD6R")
      (footprint "New footprint 1")
      (description "Test Point .6mm")
      (libsource (lib "Space Concordia") (part "TP"))
    )
    (comp (ref "TP33")
      (value "TPAD6R")
      (footprint "New footprint 1")
      (description "Test Point .6mm")
      (libsource (lib "Space Concordia") (part "TP"))
    )
    (comp (ref "TP34")
      (value "TPAD6R")
      (footprint "New footprint 1")
      (description "Test Point .6mm")
      (libsource (lib "Space Concordia") (part "TP"))
    )
    (comp (ref "U1")
      (value "MAX96724FGTN/V+")
      (footprint "MAX96724FGTN_V+-Footprint-1")
      (description "Quad Tunneling GMSL2/1 to CSI-2 Deserializer")
      (libsource (lib "") (part "MAX96724FGTN_V+-Symbol-1_1"))
    )
    (comp (ref "U2")
      (value "LD1117S18TR")
      (footprint "SOT-223_M")
      (description "Fixed Low Drop Positive Voltage Regulator, 1.8V, 4-Pin SOT-223, Tape and Reel")
      (libsource (lib "Altium Content Vault") (part "PM-REG-LD1117-SOT4"))
    )
    (comp (ref "U3")
      (value "LD1117S12TR")
      (footprint "SOT-223_M")
      (description "Fixed Low Drop Positive Voltage Regulator, 1.2V, 4-Pin SOT-223, Tape and Reel")
      (libsource (lib "Altium Content Vault") (part "PM-REG-LD1117-SOT4"))
    )
    (comp (ref "Y1")
      (value "ABM8G-25.000MHZ-18-D2Y-T")
      (footprint "FP-ABM8G-MFG")
      (description "Crystal 25MHz ±20ppm (Tol) ±30ppm (Stability) 18pF FUND 60Ω 4-Pin SMD T/R")
      (fields (field (name "TOLERANCE") "20ppm"))
      (libsource (lib "Altium Content Vault") (part "48e526d86b7f2615d98721063c72f49"))
    )
  )
  (nets
    (net (code "1") (name "/CAM_1V2") (class "Default")
      (node (ref "C59") (pin "1") (pinfunction "1_1") (pintype "passive"))
      (node (ref "R38") (pin "1") (pinfunction "1_1") (pintype "passive"))
      (node (ref "R39") (pin "1") (pinfunction "1_1") (pintype "passive"))
      (node (ref "R43") (pin "1") (pinfunction "1_1") (pintype "passive"))
      (node (ref "U3") (pin "2") (pinfunction "VOUT_2") (pintype "power_in"))
      (node (ref "U3") (pin "4") (pinfunction "VOUT_4") (pintype "power_in"))
    )
    (net (code "2") (name "/CAM_1V8") (class "Default")
      (node (ref "C45") (pin "1") (pinfunction "1_1") (pintype "passive"))
      (node (ref "R40") (pin "1") (pinfunction "1_1") (pintype "passive"))
      (node (ref "R41") (pin "1") (pinfunction "1_1") (pintype "passive"))
      (node (ref "U2") (pin "2") (pinfunction "VOUT_2") (pintype "power_in"))
      (node (ref "U2") (pin "4") (pinfunction "VOUT_4") (pintype "power_in"))
    )
    (net (code "3") (name "/CAM_I2C_SCL") (class "Default")
      (node (ref "R26") (pin "1") (pinfunction "1_1") (pintype "passive"))
      (node (ref "TP24") (pin "1") (pinfunction "TP_1") (pintype "passive"))
      (node (ref "U1") (pin "29") (pinfunction "SCL_29") (pintype "passive"))
    )
    (net (code "4") (name "/CAM_I2C_SDA") (class "Default")
      (node (ref "R25") (pin "1") (pinfunction "1_1") (pintype "passive"))
      (node (ref "TP22") (pin "1") (pinfunction "TP_1") (pintype "passive"))
      (node (ref "U1") (pin "28") (pinfunction "SDA_28") (pintype "passive"))
    )
    (net (code "5") (name "/CFG0") (class "Default")
      (node (ref "R32") (pin "1") (pinfunction "1_1") (pintype "passive"))
      (node (ref "R35") (pin "2") (pinfunction "2_2") (pintype "passive"))
      (node (ref "TP34") (pin "1") (pinfunction "TP_1") (pintype "passive"))
      (node (ref "U1") (pin "4") (pinfunction "CFG0_4") (pintype "input"))
    )
    (net (code "6") (name "/CKA_N") (class "Default")
      (node (ref "C69") (pin "2") (pinfunction "2_2") (pintype "passive"))
      (node (ref "U1") (pin "40") (pinfunction "CKAN_40") (pintype "bidirectional"))
    )
    (net (code "7") (name "/CKA_P") (class "Default")
      (node (ref "C68") (pin "2") (pinfunction "2_2") (pintype "passive"))
      (node (ref "U1") (pin "39") (pinfunction "CKAP_39") (pintype "bidirectional"))
    )
    (net (code "8") (name "/CKB_N") (class "Default")
      (node (ref "C41") (pin "1") (pinfunction "1_1") (pintype "passive"))
      (node (ref "U1") (pin "46") (pinfunction "NC/CKBN_46") (pintype "passive"))
    )
    (net (code "9") (name "/CKB_P") (class "Default")
      (node (ref "C38") (pin "1") (pinfunction "1_1") (pintype "passive"))
      (node (ref "U1") (pin "45") (pinfunction "NC/CKBP_45") (pintype "passive"))
    )
    (net (code "10") (name "/CKC_N") (class "Default")
      (node (ref "C27") (pin "1") (pinfunction "1_1") (pintype "passive"))
      (node (ref "U1") (pin "34") (pinfunction "CKCN_34") (pintype "bidirectional"))
    )
    (net (code "11") (name "/CKC_P") (class "Default")
      (node (ref "C24") (pin "1") (pinfunction "1_1") (pintype "passive"))
      (node (ref "U1") (pin "33") (pinfunction "CKCP_33") (pintype "bidirectional"))
    )
    (net (code "12") (name "/CKF_N") (class "Default")
      (node (ref "C71") (pin "2") (pinfunction "2_2") (pintype "passive"))
      (node (ref "U1") (pin "52") (pinfunction "NC/CKFN_52") (pintype "passive"))
    )
    (net (code "13") (name "/CKF_P") (class "Default")
      (node (ref "C70") (pin "2") (pinfunction "2_2") (pintype "passive"))
      (node (ref "U1") (pin "51") (pinfunction "NC/CKFP_51") (pintype "passive"))
    )
    (net (code "14") (name "/CSI0_CKALT_N") (class "Default")
      (node (ref "C69") (pin "1") (pinfunction "1_1") (pintype "passive"))
    )
    (net (code "15") (name "/CSI0_CKALT_P") (class "Default")
      (node (ref "C68") (pin "1") (pinfunction "1_1") (pintype "passive"))
    )
    (net (code "16") (name "/CSI0_CK_N") (class "Default")
      (node (ref "C27") (pin "2") (pinfunction "2_2") (pintype "passive"))
    )
    (net (code "17") (name "/CSI0_CK_P") (class "Default")
      (node (ref "C24") (pin "2") (pinfunction "2_2") (pintype "passive"))
    )
    (net (code "18") (name "/CSI0_D0_N") (class "Default")
      (node (ref "C15") (pin "2") (pinfunction "2_2") (pintype "passive"))
    )
    (net (code "19") (name "/CSI0_D0_P") (class "Default")
      (node (ref "C14") (pin "2") (pinfunction "2_2") (pintype "passive"))
    )
    (net (code "20") (name "/CSI0_D1_N") (class "Default")
      (node (ref "C17") (pin "2") (pinfunction "2_2") (pintype "passive"))
    )
    (net (code "21") (name "/CSI0_D1_P") (class "Default")
      (node (ref "C16") (pin "2") (pinfunction "2_2") (pintype "passive"))
    )
    (net (code "22") (name "/CSI0_D2_N") (class "Default")
      (node (ref "C19") (pin "2") (pinfunction "2_2") (pintype "passive"))
    )
    (net (code "23") (name "/CSI0_D2_P") (class "Default")
      (node (ref "C18") (pin "2") (pinfunction "2_2") (pintype "passive"))
    )
    (net (code "24") (name "/CSI0_D3_N") (class "Default")
      (node (ref "C23") (pin "2") (pinfunction "2_2") (pintype "passive"))
    )
    (net (code "25") (name "/CSI0_D3_P") (class "Default")
      (node (ref "C22") (pin "2") (pinfunction "2_2") (pintype "passive"))
    )
    (net (code "26") (name "/CSI1_CKALT_N") (class "Default")
      (node (ref "C71") (pin "1") (pinfunction "1_1") (pintype "passive"))
    )
    (net (code "27") (name "/CSI1_CKALT_P") (class "Default")
      (node (ref "C70") (pin "1") (pinfunction "1_1") (pintype "passive"))
    )
    (net (code "28") (name "/CSI1_CK_N") (class "Default")
      (node (ref "C41") (pin "2") (pinfunction "2_2") (pintype "passive"))
    )
    (net (code "29") (name "/CSI1_CK_P") (class "Default")
      (node (ref "C38") (pin "2") (pinfunction "2_2") (pintype "passive"))
    )
    (net (code "30") (name "/CSI1_D0_N") (class "Default")
      (node (ref "C29") (pin "2") (pinfunction "2_2") (pintype "passive"))
    )
    (net (code "31") (name "/CSI1_D0_P") (class "Default")
      (node (ref "C28") (pin "2") (pinfunction "2_2") (pintype "passive"))
    )
    (net (code "32") (name "/CSI1_D1_N") (class "Default")
      (node (ref "C31") (pin "2") (pinfunction "2_2") (pintype "passive"))
    )
    (net (code "33") (name "/CSI1_D1_P") (class "Default")
      (node (ref "C30") (pin "2") (pinfunction "2_2") (pintype "passive"))
    )
    (net (code "34") (name "/CSI1_D2_N") (class "Default")
      (node (ref "C33") (pin "2") (pinfunction "2_2") (pintype "passive"))
    )
    (net (code "35") (name "/CSI1_D2_P") (class "Default")
      (node (ref "C32") (pin "2") (pinfunction "2_2") (pintype "passive"))
    )
    (net (code "36") (name "/CSI1_D3_N") (class "Default")
      (node (ref "C37") (pin "2") (pinfunction "2_2") (pintype "passive"))
    )
    (net (code "37") (name "/CSI1_D3_P") (class "Default")
      (node (ref "C36") (pin "2") (pinfunction "2_2") (pintype "passive"))
    )
    (net (code "38") (name "/DA0_N") (class "Default")
      (node (ref "C15") (pin "1") (pinfunction "1_1") (pintype "passive"))
      (node (ref "U1") (pin "32") (pinfunction "DA0N_32") (pintype "bidirectional"))
    )
    (net (code "39") (name "/DA0_P") (class "Default")
      (node (ref "C14") (pin "1") (pinfunction "1_1") (pintype "passive"))
      (node (ref "U1") (pin "31") (pinfunction "DA0P_31") (pintype "bidirectional"))
    )
    (net (code "40") (name "/DA1_N") (class "Default")
      (node (ref "C17") (pin "1") (pinfunction "1_1") (pintype "passive"))
      (node (ref "U1") (pin "36") (pinfunction "DA1N_36") (pintype "bidirectional"))
    )
    (net (code "41") (name "/DA1_P") (class "Default")
      (node (ref "C16") (pin "1") (pinfunction "1_1") (pintype "passive"))
      (node (ref "U1") (pin "35") (pinfunction "DA1P_35") (pintype "bidirectional"))
    )
    (net (code "42") (name "/DA2_N") (class "Default")
      (node (ref "C19") (pin "1") (pinfunction "1_1") (pintype "passive"))
      (node (ref "U1") (pin "38") (pinfunction "DA2N_38") (pintype "bidirectional"))
    )
    (net (code "43") (name "/DA2_P") (class "Default")
      (node (ref "C18") (pin "1") (pinfunction "1_1") (pintype "passive"))
      (node (ref "U1") (pin "37") (pinfunction "DA2P_37") (pintype "bidirectional"))
    )
    (net (code "44") (name "/DA3_N") (class "Default")
      (node (ref "C23") (pin "1") (pinfunction "1_1") (pintype "passive"))
      (node (ref "U1") (pin "42") (pinfunction "DA3N_42") (pintype "bidirectional"))
    )
    (net (code "45") (name "/DA3_P") (class "Default")
      (node (ref "C22") (pin "1") (pinfunction "1_1") (pintype "passive"))
      (node (ref "U1") (pin "41") (pinfunction "DA3P_41") (pintype "bidirectional"))
    )
    (net (code "46") (name "/DB0_N") (class "Default")
      (node (ref "C29") (pin "1") (pinfunction "1_1") (pintype "passive"))
      (node (ref "U1") (pin "44") (pinfunction "NC/DB0N_44") (pintype "passive"))
    )
    (net (code "47") (name "/DB0_P") (class "Default")
      (node (ref "C28") (pin "1") (pinfunction "1_1") (pintype "passive"))
      (node (ref "U1") (pin "43") (pinfunction "NC/DB0P_43") (pintype "passive"))
    )
    (net (code "48") (name "/DB1_N") (class "Default")
      (node (ref "C31") (pin "1") (pinfunction "1_1") (pintype "passive"))
      (node (ref "U1") (pin "48") (pinfunction "NC/DB1N_48") (pintype "passive"))
    )
    (net (code "49") (name "/DB1_P") (class "Default")
      (node (ref "C30") (pin "1") (pinfunction "1_1") (pintype "passive"))
      (node (ref "U1") (pin "47") (pinfunction "NC/DB1P_47") (pintype "passive"))
    )
    (net (code "50") (name "/DB2_N") (class "Default")
      (node (ref "C33") (pin "1") (pinfunction "1_1") (pintype "passive"))
      (node (ref "U1") (pin "50") (pinfunction "NC/DB2N_50") (pintype "passive"))
    )
    (net (code "51") (name "/DB2_P") (class "Default")
      (node (ref "C32") (pin "1") (pinfunction "1_1") (pintype "passive"))
      (node (ref "U1") (pin "49") (pinfunction "NC/DB2P_49") (pintype "passive"))
    )
    (net (code "52") (name "/DB3_N") (class "Default")
      (node (ref "C37") (pin "1") (pinfunction "1_1") (pintype "passive"))
      (node (ref "U1") (pin "54") (pinfunction "NC/DB3N_54") (pintype "passive"))
    )
    (net (code "53") (name "/DB3_P") (class "Default")
      (node (ref "C36") (pin "1") (pinfunction "1_1") (pintype "passive"))
      (node (ref "U1") (pin "53") (pinfunction "NC/DB3P_53") (pintype "passive"))
    )
    (net (code "54") (name "/MFP0") (class "Default")
      (node (ref "TP26") (pin "1") (pinfunction "TP_1") (pintype "passive"))
      (node (ref "U1") (pin "1") (pinfunction "MFP0_1") (pintype "bidirectional"))
    )
    (net (code "55") (name "/MFP1") (class "Default")
      (node (ref "TP28") (pin "1") (pinfunction "TP_1") (pintype "passive"))
      (node (ref "U1") (pin "2") (pinfunction "MFP1_2") (pintype "bidirectional"))
    )
    (net (code "56") (name "/MFP2") (class "Default")
      (node (ref "TP30") (pin "1") (pinfunction "TP_1") (pintype "passive"))
      (node (ref "U1") (pin "3") (pinfunction "MFP2_3") (pintype "bidirectional"))
    )
    (net (code "57") (name "/MFP3") (class "Default")
      (node (ref "TP23") (pin "1") (pinfunction "TP_1") (pintype "passive"))
      (node (ref "U1") (pin "12") (pinfunction "MFP3_12") (pintype "bidirectional"))
    )
    (net (code "58") (name "/MFP4") (class "Default")
      (node (ref "TP25") (pin "1") (pinfunction "TP_1") (pintype "passive"))
      (node (ref "U1") (pin "13") (pinfunction "MFP4_13") (pintype "bidirectional"))
    )
    (net (code "59") (name "/MFP5") (class "Default")
      (node (ref "TP27") (pin "1") (pinfunction "TP_1") (pintype "passive"))
      (node (ref "U1") (pin "14") (pinfunction "MFP5_14") (pintype "bidirectional"))
    )
    (net (code "60") (name "/MFP6") (class "Default")
      (node (ref "R31") (pin "1") (pinfunction "1_1") (pintype "passive"))
      (node (ref "R34") (pin "2") (pinfunction "2_2") (pintype "passive"))
      (node (ref "TP29") (pin "1") (pinfunction "TP_1") (pintype "passive"))
      (node (ref "U1") (pin "25") (pinfunction "CFG1/MFP6_25") (pintype "bidirectional"))
    )
    (net (code "61") (name "/MFP7") (class "Default")
      (node (ref "TP31") (pin "1") (pinfunction "TP_1") (pintype "passive"))
      (node (ref "U1") (pin "26") (pinfunction "SDA1/MFP7_26") (pintype "bidirectional"))
    )
    (net (code "62") (name "/MFP8") (class "Default")
      (node (ref "TP33") (pin "1") (pinfunction "TP_1") (pintype "passive"))
      (node (ref "U1") (pin "27") (pinfunction "SCL1/MFP8_27") (pintype "bidirectional"))
    )
    (net (code "63") (name "/PoC_A") (class "Default")
      (node (ref "C20") (pin "2") (pinfunction "2_2") (pintype "passive"))
      (node (ref "D1") (pin "1") (pinfunction "IO1_1") (pintype "bidirectional"))
      (node (ref "D1") (pin "10") (pinfunction "NC_10") (pintype "passive"))
      (node (ref "J8") (pin "2") (pinfunction "2_2") (pintype "passive"))
      (node (ref "L2") (pin "2") (pinfunction "2_2") (pintype "passive"))
    )
    (net (code "64") (name "/PoC_B") (class "Default")
      (node (ref "C21") (pin "2") (pinfunction "2_2") (pintype "passive"))
      (node (ref "D2") (pin "5") (pinfunction "IO4_5") (pintype "bidirectional"))
      (node (ref "D2") (pin "6") (pinfunction "NC_6") (pintype "passive"))
      (node (ref "J8") (pin "1") (pinfunction "1_1") (pintype "passive"))
      (node (ref "L4") (pin "2") (pinfunction "2_2") (pintype "passive"))
    )
    (net (code "65") (name "/PoC_C") (class "Default")
      (node (ref "C34") (pin "2") (pinfunction "2_2") (pintype "passive"))
      (node (ref "D3") (pin "1") (pinfunction "IO1_1") (pintype "bidirectional"))
      (node (ref "D3") (pin "10") (pinfunction "NC_10") (pintype "passive"))
      (node (ref "J8") (pin "4") (pinfunction "4_4") (pintype "passive"))
      (node (ref "L8") (pin "2") (pinfunction "2_2") (pintype "passive"))
    )
    (net (code "66") (name "/PoC_D") (class "Default")
      (node (ref "C35") (pin "2") (pinfunction "2_2") (pintype "passive"))
      (node (ref "D4") (pin "5") (pinfunction "IO4_5") (pintype "bidirectional"))
      (node (ref "D4") (pin "6") (pinfunction "NC_6") (pintype "passive"))
      (node (ref "J8") (pin "3") (pinfunction "3_3") (pintype "passive"))
      (node (ref "L6") (pin "2") (pinfunction "2_2") (pintype "passive"))
    )
    (net (code "67") (name "/PoC_PWR") (class "Default")
      (node (ref "F2") (pin "1") (pinfunction "1_1") (pintype "passive"))
      (node (ref "F3") (pin "1") (pinfunction "1_1") (pintype "passive"))
      (node (ref "F4") (pin "1") (pinfunction "1_1") (pintype "passive"))
      (node (ref "F5") (pin "1") (pinfunction "1_1") (pintype "passive"))
    )
    (net (code "68") (name "/SIOA_N") (class "Default")
      (node (ref "C25") (pin "1") (pinfunction "1_1") (pintype "passive"))
      (node (ref "U1") (pin "22") (pinfunction "SIOAN_22") (pintype "bidirectional"))
    )
    (net (code "69") (name "/SIOA_P") (class "Default")
      (node (ref "C20") (pin "1") (pinfunction "1_1") (pintype "passive"))
      (node (ref "U1") (pin "23") (pinfunction "SIOAP_23") (pintype "bidirectional"))
    )
    (net (code "70") (name "/SIOB_N") (class "Default")
      (node (ref "C26") (pin "1") (pinfunction "1_1") (pintype "passive"))
      (node (ref "U1") (pin "19") (pinfunction "SIOBN_19") (pintype "bidirectional"))
    )
    (net (code "71") (name "/SIOB_P") (class "Default")
      (node (ref "C21") (pin "1") (pinfunction "1_1") (pintype "passive"))
      (node (ref "U1") (pin "18") (pinfunction "SIOBP_18") (pintype "bidirectional"))
    )
    (net (code "72") (name "/SIOC_N") (class "Default")
      (node (ref "C39") (pin "1") (pinfunction "1_1") (pintype "passive"))
      (node (ref "U1") (pin "9") (pinfunction "SIOCN_9") (pintype "bidirectional"))
    )
    (net (code "73") (name "/SIOC_P") (class "Default")
      (node (ref "C34") (pin "1") (pinfunction "1_1") (pintype "passive"))
      (node (ref "U1") (pin "10") (pinfunction "SIOCP_10") (pintype "bidirectional"))
    )
    (net (code "74") (name "/SIOD_N") (class "Default")
      (node (ref "C40") (pin "1") (pinfunction "1_1") (pintype "passive"))
      (node (ref "U1") (pin "6") (pinfunction "SIODN_6") (pintype "bidirectional"))
    )
    (net (code "75") (name "/SIOD_P") (class "Default")
      (node (ref "C35") (pin "1") (pinfunction "1_1") (pintype "passive"))
      (node (ref "U1") (pin "5") (pinfunction "SIODP_5") (pintype "bidirectional"))
    )
    (net (code "76") (name "/X25_N") (class "Default")
      (node (ref "C43") (pin "2") (pinfunction "2_2") (pintype "passive"))
      (node (ref "U1") (pin "16") (pinfunction "X2_16") (pintype "passive"))
      (node (ref "Y1") (pin "3") (pinfunction "3_3") (pintype "passive"))
    )
    (net (code "77") (name "/X25_P") (class "Default")
      (node (ref "C42") (pin "2") (pinfunction "2_2") (pintype "passive"))
      (node (ref "U1") (pin "15") (pinfunction "X1/OSC_15") (pintype "passive"))
      (node (ref "Y1") (pin "1") (pinfunction "1_1") (pintype "passive"))
    )
    (net (code "78") (name "/XRES") (class "Default")
      (node (ref "R27") (pin "2") (pinfunction "2_2") (pintype "passive"))
      (node (ref "U1") (pin "17") (pinfunction "XRES_17") (pintype "passive"))
    )
    (net (code "79") (name "/nPWDN") (class "Default")
      (node (ref "R28") (pin "1") (pinfunction "1_1") (pintype "passive"))
      (node (ref "TP32") (pin "1") (pinfunction "TP_1") (pintype "passive"))
      (node (ref "U1") (pin "11") (pinfunction "PWDNB_11") (pintype "input"))
    )
    (net (code "80") (name "3V3_AUX") (class "Default")
      (node (ref "R25") (pin "2") (pinfunction "2_2") (pintype "passive"))
      (node (ref "R26") (pin "2") (pinfunction "2_2") (pintype "passive"))
      (node (ref "R28") (pin "2") (pinfunction "2_2") (pintype "passive"))
      (node (ref "R31") (pin "2") (pinfunction "2_2") (pintype "passive"))
      (node (ref "R32") (pin "2") (pinfunction "2_2") (pintype "passive"))
      (node (ref "R42") (pin "1") (pinfunction "1_1") (pintype "passive"))
    )
    (net (code "81") (name "GND") (class "Default")
      (node (ref "C42") (pin "1") (pinfunction "1_1") (pintype "passive"))
      (node (ref "C43") (pin "1") (pinfunction "1_1") (pintype "passive"))
      (node (ref "C44") (pin "1") (pinfunction "1_1") (pintype "passive"))
      (node (ref "C45") (pin "2") (pinfunction "2_2") (pintype "passive"))
      (node (ref "C46") (pin "1") (pinfunction "1_1") (pintype "passive"))
      (node (ref "C47") (pin "1") (pinfunction "1_1") (pintype "passive"))
      (node (ref "C48") (pin "1") (pinfunction "1_1") (pintype "passive"))
      (node (ref "C49") (pin "1") (pinfunction "1_1") (pintype "passive"))
      (node (ref "C50") (pin "1") (pinfunction "1_1") (pintype "passive"))
      (node (ref "C51") (pin "1") (pinfunction "1_1") (pintype "passive"))
      (node (ref "C52") (pin "1") (pinfunction "1_1") (pintype "passive"))
      (node (ref "C53") (pin "1") (pinfunction "1_1") (pintype "passive"))
      (node (ref "C54") (pin "1") (pinfunction "1_1") (pintype "passive"))
      (node (ref "C55") (pin "1") (pinfunction "1_1") (pintype "passive"))
      (node (ref "C56") (pin "1") (pinfunction "1_1") (pintype "passive"))
      (node (ref "C57") (pin "1") (pinfunction "1_1") (pintype "passive"))
      (node (ref "C58") (pin "1") (pinfunction "1_1") (pintype "passive"))
      (node (ref "C59") (pin "2") (pinfunction "2_2") (pintype "passive"))
      (node (ref "C60") (pin "1") (pinfunction "1_1") (pintype "passive"))
      (node (ref "C61") (pin "1") (pinfunction "1_1") (pintype "passive"))
      (node (ref "C62") (pin "1") (pinfunction "1_1") (pintype "passive"))
      (node (ref "C63") (pin "1") (pinfunction "1_1") (pintype "passive"))
      (node (ref "C64") (pin "2") (pinfunction "2_2") (pintype "passive"))
      (node (ref "C65") (pin "2") (pinfunction "2_2") (pintype "passive"))
      (node (ref "C66") (pin "2") (pinfunction "2_2") (pintype "passive"))
      (node (ref "C67") (pin "2") (pinfunction "2_2") (pintype "passive"))
      (node (ref "D1") (pin "3") (pinfunction "GND_3") (pintype "power_in"))
      (node (ref "D1") (pin "8") (pinfunction "GND_8") (pintype "power_in"))
      (node (ref "D2") (pin "3") (pinfunction "GND_3") (pintype "power_in"))
      (node (ref "D2") (pin "8") (pinfunction "GND_8") (pintype "power_in"))
      (node (ref "D3") (pin "3") (pinfunction "GND_3") (pintype "power_in"))
      (node (ref "D3") (pin "8") (pinfunction "GND_8") (pintype "power_in"))
      (node (ref "D4") (pin "3") (pinfunction "GND_3") (pintype "power_in"))
      (node (ref "D4") (pin "8") (pinfunction "GND_8") (pintype "power_in"))
      (node (ref "J8") (pin "MH1") (pinfunction "MH1_MH1") (pintype "passive"))
      (node (ref "J8") (pin "MH2") (pinfunction "MH2_MH2") (pintype "passive"))
      (node (ref "J8") (pin "MH3") (pinfunction "MH3_MH3") (pintype "passive"))
      (node (ref "J8") (pin "MH4") (pinfunction "MH4_MH4") (pintype "passive"))
      (node (ref "J8") (pin "MH5") (pinfunction "MH5_MH5") (pintype "passive"))
      (node (ref "R27") (pin "1") (pinfunction "1_1") (pintype "passive"))
      (node (ref "R29") (pin "1") (pinfunction "1_1") (pintype "passive"))
      (node (ref "R30") (pin "1") (pinfunction "1_1") (pintype "passive"))
      (node (ref "R34") (pin "1") (pinfunction "1_1") (pintype "passive"))
      (node (ref "R35") (pin "1") (pinfunction "1_1") (pintype "passive"))
      (node (ref "R36") (pin "1") (pinfunction "1_1") (pintype "passive"))
      (node (ref "R37") (pin "1") (pinfunction "1_1") (pintype "passive"))
      (node (ref "U1") (pin "57") (pinfunction "GND_(EP)_57") (pintype "power_in"))
      (node (ref "U2") (pin "1") (pinfunction "GND_1") (pintype "power_in"))
      (node (ref "U3") (pin "1") (pinfunction "GND_1") (pintype "power_in"))
      (node (ref "Y1") (pin "2") (pinfunction "GND_2") (pintype "power_in"))
      (node (ref "Y1") (pin "4") (pinfunction "GND_4") (pintype "power_in"))
    )
    (net (code "82") (name "LO_VCC") (class "Default")
      (node (ref "C44") (pin "2") (pinfunction "2_2") (pintype "passive"))
      (node (ref "C58") (pin "2") (pinfunction "2_2") (pintype "passive"))
      (node (ref "U2") (pin "3") (pinfunction "VIN_3") (pintype "power_in"))
      (node (ref "U3") (pin "3") (pinfunction "VIN_3") (pintype "power_in"))
    )
    (net (code "83") (name "Net-(C25-Pad2)") (class "Default")
      (node (ref "C25") (pin "2") (pinfunction "2_2") (pintype "passive"))
      (node (ref "R29") (pin "2") (pinfunction "2_2") (pintype "passive"))
    )
    (net (code "84") (name "Net-(C26-Pad2)") (class "Default")
      (node (ref "C26") (pin "2") (pinfunction "2_2") (pintype "passive"))
      (node (ref "R30") (pin "2") (pinfunction "2_2") (pintype "passive"))
    )
    (net (code "85") (name "Net-(C39-Pad2)") (class "Default")
      (node (ref "C39") (pin "2") (pinfunction "2_2") (pintype "passive"))
      (node (ref "R36") (pin "2") (pinfunction "2_2") (pintype "passive"))
    )
    (net (code "86") (name "Net-(C40-Pad2)") (class "Default")
      (node (ref "C40") (pin "2") (pinfunction "2_2") (pintype "passive"))
      (node (ref "R37") (pin "2") (pinfunction "2_2") (pintype "passive"))
    )
    (net (code "87") (name "Net-(C46-Pad2)") (class "Default")
      (node (ref "C46") (pin "2") (pinfunction "2_2") (pintype "passive"))
      (node (ref "C47") (pin "2") (pinfunction "2_2") (pintype "passive"))
      (node (ref "U1") (pin "8") (pinfunction "CAP_VDD_8") (pintype "power_in"))
    )
    (net (code "88") (name "Net-(C48-Pad2)") (class "Default")
      (node (ref "C48") (pin "2") (pinfunction "2_2") (pintype "passive"))
      (node (ref "C49") (pin "2") (pinfunction "2_2") (pintype "passive"))
      (node (ref "U1") (pin "20") (pinfunction "CAP_VDD_20") (pintype "power_in"))
    )
    (net (code "89") (name "Net-(C50-Pad2)") (class "Default")
      (node (ref "C50") (pin "2") (pinfunction "2_2") (pintype "passive"))
      (node (ref "C51") (pin "2") (pinfunction "2_2") (pintype "passive"))
      (node (ref "R38") (pin "2") (pinfunction "2_2") (pintype "passive"))
      (node (ref "U1") (pin "55") (pinfunction "VDD_55") (pintype "power_in"))
    )
    (net (code "90") (name "Net-(C52-Pad2)") (class "Default")
      (node (ref "C52") (pin "2") (pinfunction "2_2") (pintype "passive"))
      (node (ref "C53") (pin "2") (pinfunction "2_2") (pintype "passive"))
      (node (ref "R39") (pin "2") (pinfunction "2_2") (pintype "passive"))
      (node (ref "U1") (pin "56") (pinfunction "VDD_56") (pintype "power_in"))
    )
    (net (code "91") (name "Net-(C54-Pad2)") (class "Default")
      (node (ref "C54") (pin "2") (pinfunction "2_2") (pintype "passive"))
      (node (ref "C55") (pin "2") (pinfunction "2_2") (pintype "passive"))
      (node (ref "R40") (pin "2") (pinfunction "2_2") (pintype "passive"))
      (node (ref "U1") (pin "7") (pinfunction "VDD18_7") (pintype "power_in"))
    )
    (net (code "92") (name "Net-(C56-Pad2)") (class "Default")
      (node (ref "C56") (pin "2") (pinfunction "2_2") (pintype "passive"))
      (node (ref "C57") (pin "2") (pinfunction "2_2") (pintype "passive"))
      (node (ref "R41") (pin "2") (pinfunction "2_2") (pintype "passive"))
      (node (ref "U1") (pin "21") (pinfunction "VDD18_21") (pintype "power_in"))
    )
    (net (code "93") (name "Net-(C64-Pad1)") (class "Default")
      (node (ref "C64") (pin "1") (pinfunction "1_1") (pintype "passive"))
      (node (ref "L1") (pin "1") (pinfunction "1_1") (pintype "passive"))
      (node (ref "L9") (pin "2") (pinfunction "2_2") (pintype "passive"))
      (node (ref "R44") (pin "1") (pinfunction "1_1") (pintype "passive"))
    )
    (net (code "94") (name "Net-(C65-Pad1)") (class "Default")
      (node (ref "C65") (pin "1") (pinfunction "1_1") (pintype "passive"))
      (node (ref "L10") (pin "2") (pinfunction "2_2") (pintype "passive"))
      (node (ref "L3") (pin "1") (pinfunction "1_1") (pintype "passive"))
      (node (ref "R45") (pin "1") (pinfunction "1_1") (pintype "passive"))
    )
    (net (code "95") (name "Net-(C66-Pad1)") (class "Default")
      (node (ref "C66") (pin "1") (pinfunction "1_1") (pintype "passive"))
      (node (ref "L11") (pin "2") (pinfunction "2_2") (pintype "passive"))
      (node (ref "L5") (pin "1") (pinfunction "1_1") (pintype "passive"))
      (node (ref "R46") (pin "1") (pinfunction "1_1") (pintype "passive"))
    )
    (net (code "96") (name "Net-(C67-Pad1)") (class "Default")
      (node (ref "C67") (pin "1") (pinfunction "1_1") (pintype "passive"))
      (node (ref "L12") (pin "2") (pinfunction "2_2") (pintype "passive"))
      (node (ref "L7") (pin "1") (pinfunction "1_1") (pintype "passive"))
      (node (ref "R47") (pin "1") (pinfunction "1_1") (pintype "passive"))
    )
    (net (code "97") (name "Net-(F2-Pad2)") (class "Default")
      (node (ref "F2") (pin "2") (pinfunction "2_2") (pintype "passive"))
      (node (ref "L9") (pin "1") (pinfunction "1_1") (pintype "passive"))
    )
    (net (code "98") (name "Net-(F3-Pad2)") (class "Default")
      (node (ref "F3") (pin "2") (pinfunction "2_2") (pintype "passive"))
      (node (ref "L10") (pin "1") (pinfunction "1_1") (pintype "passive"))
    )
    (net (code "99") (name "Net-(F4-Pad2)") (class "Default")
      (node (ref "F4") (pin "2") (pinfunction "2_2") (pintype "passive"))
      (node (ref "L11") (pin "1") (pinfunction "1_1") (pintype "passive"))
    )
    (net (code "100") (name "Net-(F5-Pad2)") (class "Default")
      (node (ref "F5") (pin "2") (pinfunction "2_2") (pintype "passive"))
      (node (ref "L12") (pin "1") (pinfunction "1_1") (pintype "passive"))
    )
    (net (code "101") (name "Net-(L1-Pad2)") (class "Default")
      (node (ref "L1") (pin "2") (pinfunction "2_2") (pintype "passive"))
      (node (ref "L2") (pin "1") (pinfunction "1_1") (pintype "passive"))
      (node (ref "R44") (pin "2") (pinfunction "2_2") (pintype "passive"))
    )
    (net (code "102") (name "Net-(L3-Pad2)") (class "Default")
      (node (ref "L3") (pin "2") (pinfunction "2_2") (pintype "passive"))
      (node (ref "L4") (pin "1") (pinfunction "1_1") (pintype "passive"))
      (node (ref "R45") (pin "2") (pinfunction "2_2") (pintype "passive"))
    )
    (net (code "103") (name "Net-(L5-Pad2)") (class "Default")
      (node (ref "L5") (pin "2") (pinfunction "2_2") (pintype "passive"))
      (node (ref "L6") (pin "1") (pinfunction "1_1") (pintype "passive"))
      (node (ref "R46") (pin "2") (pinfunction "2_2") (pintype "passive"))
    )
    (net (code "104") (name "Net-(L7-Pad2)") (class "Default")
      (node (ref "L7") (pin "2") (pinfunction "2_2") (pintype "passive"))
      (node (ref "L8") (pin "1") (pinfunction "1_1") (pintype "passive"))
      (node (ref "R47") (pin "2") (pinfunction "2_2") (pintype "passive"))
    )
    (net (code "105") (name "Net-(U1B-VDDIO)") (class "Default")
      (node (ref "C60") (pin "2") (pinfunction "2_2") (pintype "passive"))
      (node (ref "C61") (pin "2") (pinfunction "2_2") (pintype "passive"))
      (node (ref "R42") (pin "2") (pinfunction "2_2") (pintype "passive"))
      (node (ref "U1") (pin "24") (pinfunction "VDDIO_24") (pintype "power_in"))
    )
    (net (code "106") (name "Net-(U1B-VTERM)") (class "Default")
      (node (ref "C62") (pin "2") (pinfunction "2_2") (pintype "passive"))
      (node (ref "C63") (pin "2") (pinfunction "2_2") (pintype "passive"))
      (node (ref "R43") (pin "2") (pinfunction "2_2") (pintype "passive"))
      (node (ref "U1") (pin "30") (pinfunction "VTERM_30") (pintype "power_in"))
    )
    (net (code "107") (name "unconnected-(D1-IO2-Pad2)") (class "Default")
      (node (ref "D1") (pin "2") (pinfunction "IO2_2") (pintype "bidirectional"))
    )
    (net (code "108") (name "unconnected-(D1-IO3-Pad4)") (class "Default")
      (node (ref "D1") (pin "4") (pinfunction "IO3_4") (pintype "bidirectional"))
    )
    (net (code "109") (name "unconnected-(D1-IO4-Pad5)") (class "Default")
      (node (ref "D1") (pin "5") (pinfunction "IO4_5") (pintype "bidirectional"))
    )
    (net (code "110") (name "unconnected-(D1-NC-Pad6)") (class "Default")
      (node (ref "D1") (pin "6") (pinfunction "NC_6") (pintype "passive"))
    )
    (net (code "111") (name "unconnected-(D1-NC-Pad7)") (class "Default")
      (node (ref "D1") (pin "7") (pinfunction "NC_7") (pintype "passive"))
    )
    (net (code "112") (name "unconnected-(D1-NC-Pad9)") (class "Default")
      (node (ref "D1") (pin "9") (pinfunction "NC_9") (pintype "passive"))
    )
    (net (code "113") (name "unconnected-(D2-IO1-Pad1)") (class "Default")
      (node (ref "D2") (pin "1") (pinfunction "IO1_1") (pintype "bidirectional"))
    )
    (net (code "114") (name "unconnected-(D2-IO2-Pad2)") (class "Default")
      (node (ref "D2") (pin "2") (pinfunction "IO2_2") (pintype "bidirectional"))
    )
    (net (code "115") (name "unconnected-(D2-IO3-Pad4)") (class "Default")
      (node (ref "D2") (pin "4") (pinfunction "IO3_4") (pintype "bidirectional"))
    )
    (net (code "116") (name "unconnected-(D2-NC-Pad7)") (class "Default")
      (node (ref "D2") (pin "7") (pinfunction "NC_7") (pintype "passive"))
    )
    (net (code "117") (name "unconnected-(D2-NC-Pad9)") (class "Default")
      (node (ref "D2") (pin "9") (pinfunction "NC_9") (pintype "passive"))
    )
    (net (code "118") (name "unconnected-(D2-NC-Pad10)") (class "Default")
      (node (ref "D2") (pin "10") (pinfunction "NC_10") (pintype "passive"))
    )
    (net (code "119") (name "unconnected-(D3-IO2-Pad2)") (class "Default")
      (node (ref "D3") (pin "2") (pinfunction "IO2_2") (pintype "bidirectional"))
    )
    (net (code "120") (name "unconnected-(D3-IO3-Pad4)") (class "Default")
      (node (ref "D3") (pin "4") (pinfunction "IO3_4") (pintype "bidirectional"))
    )
    (net (code "121") (name "unconnected-(D3-IO4-Pad5)") (class "Default")
      (node (ref "D3") (pin "5") (pinfunction "IO4_5") (pintype "bidirectional"))
    )
    (net (code "122") (name "unconnected-(D3-NC-Pad6)") (class "Default")
      (node (ref "D3") (pin "6") (pinfunction "NC_6") (pintype "passive"))
    )
    (net (code "123") (name "unconnected-(D3-NC-Pad7)") (class "Default")
      (node (ref "D3") (pin "7") (pinfunction "NC_7") (pintype "passive"))
    )
    (net (code "124") (name "unconnected-(D3-NC-Pad9)") (class "Default")
      (node (ref "D3") (pin "9") (pinfunction "NC_9") (pintype "passive"))
    )
    (net (code "125") (name "unconnected-(D4-IO1-Pad1)") (class "Default")
      (node (ref "D4") (pin "1") (pinfunction "IO1_1") (pintype "bidirectional"))
    )
    (net (code "126") (name "unconnected-(D4-IO2-Pad2)") (class "Default")
      (node (ref "D4") (pin "2") (pinfunction "IO2_2") (pintype "bidirectional"))
    )
    (net (code "127") (name "unconnected-(D4-IO3-Pad4)") (class "Default")
      (node (ref "D4") (pin "4") (pinfunction "IO3_4") (pintype "bidirectional"))
    )
    (net (code "128") (name "unconnected-(D4-NC-Pad7)") (class "Default")
      (node (ref "D4") (pin "7") (pinfunction "NC_7") (pintype "passive"))
    )
    (net (code "129") (name "unconnected-(D4-NC-Pad9)") (class "Default")
      (node (ref "D4") (pin "9") (pinfunction "NC_9") (pintype "passive"))
    )
    (net (code "130") (name "unconnected-(D4-NC-Pad10)") (class "Default")
      (node (ref "D4") (pin "10") (pinfunction "NC_10") (pintype "passive"))
    )
  )
)
